# DIO-BNC.net
KiCad netlist of a schematic drawn in Altium Designer
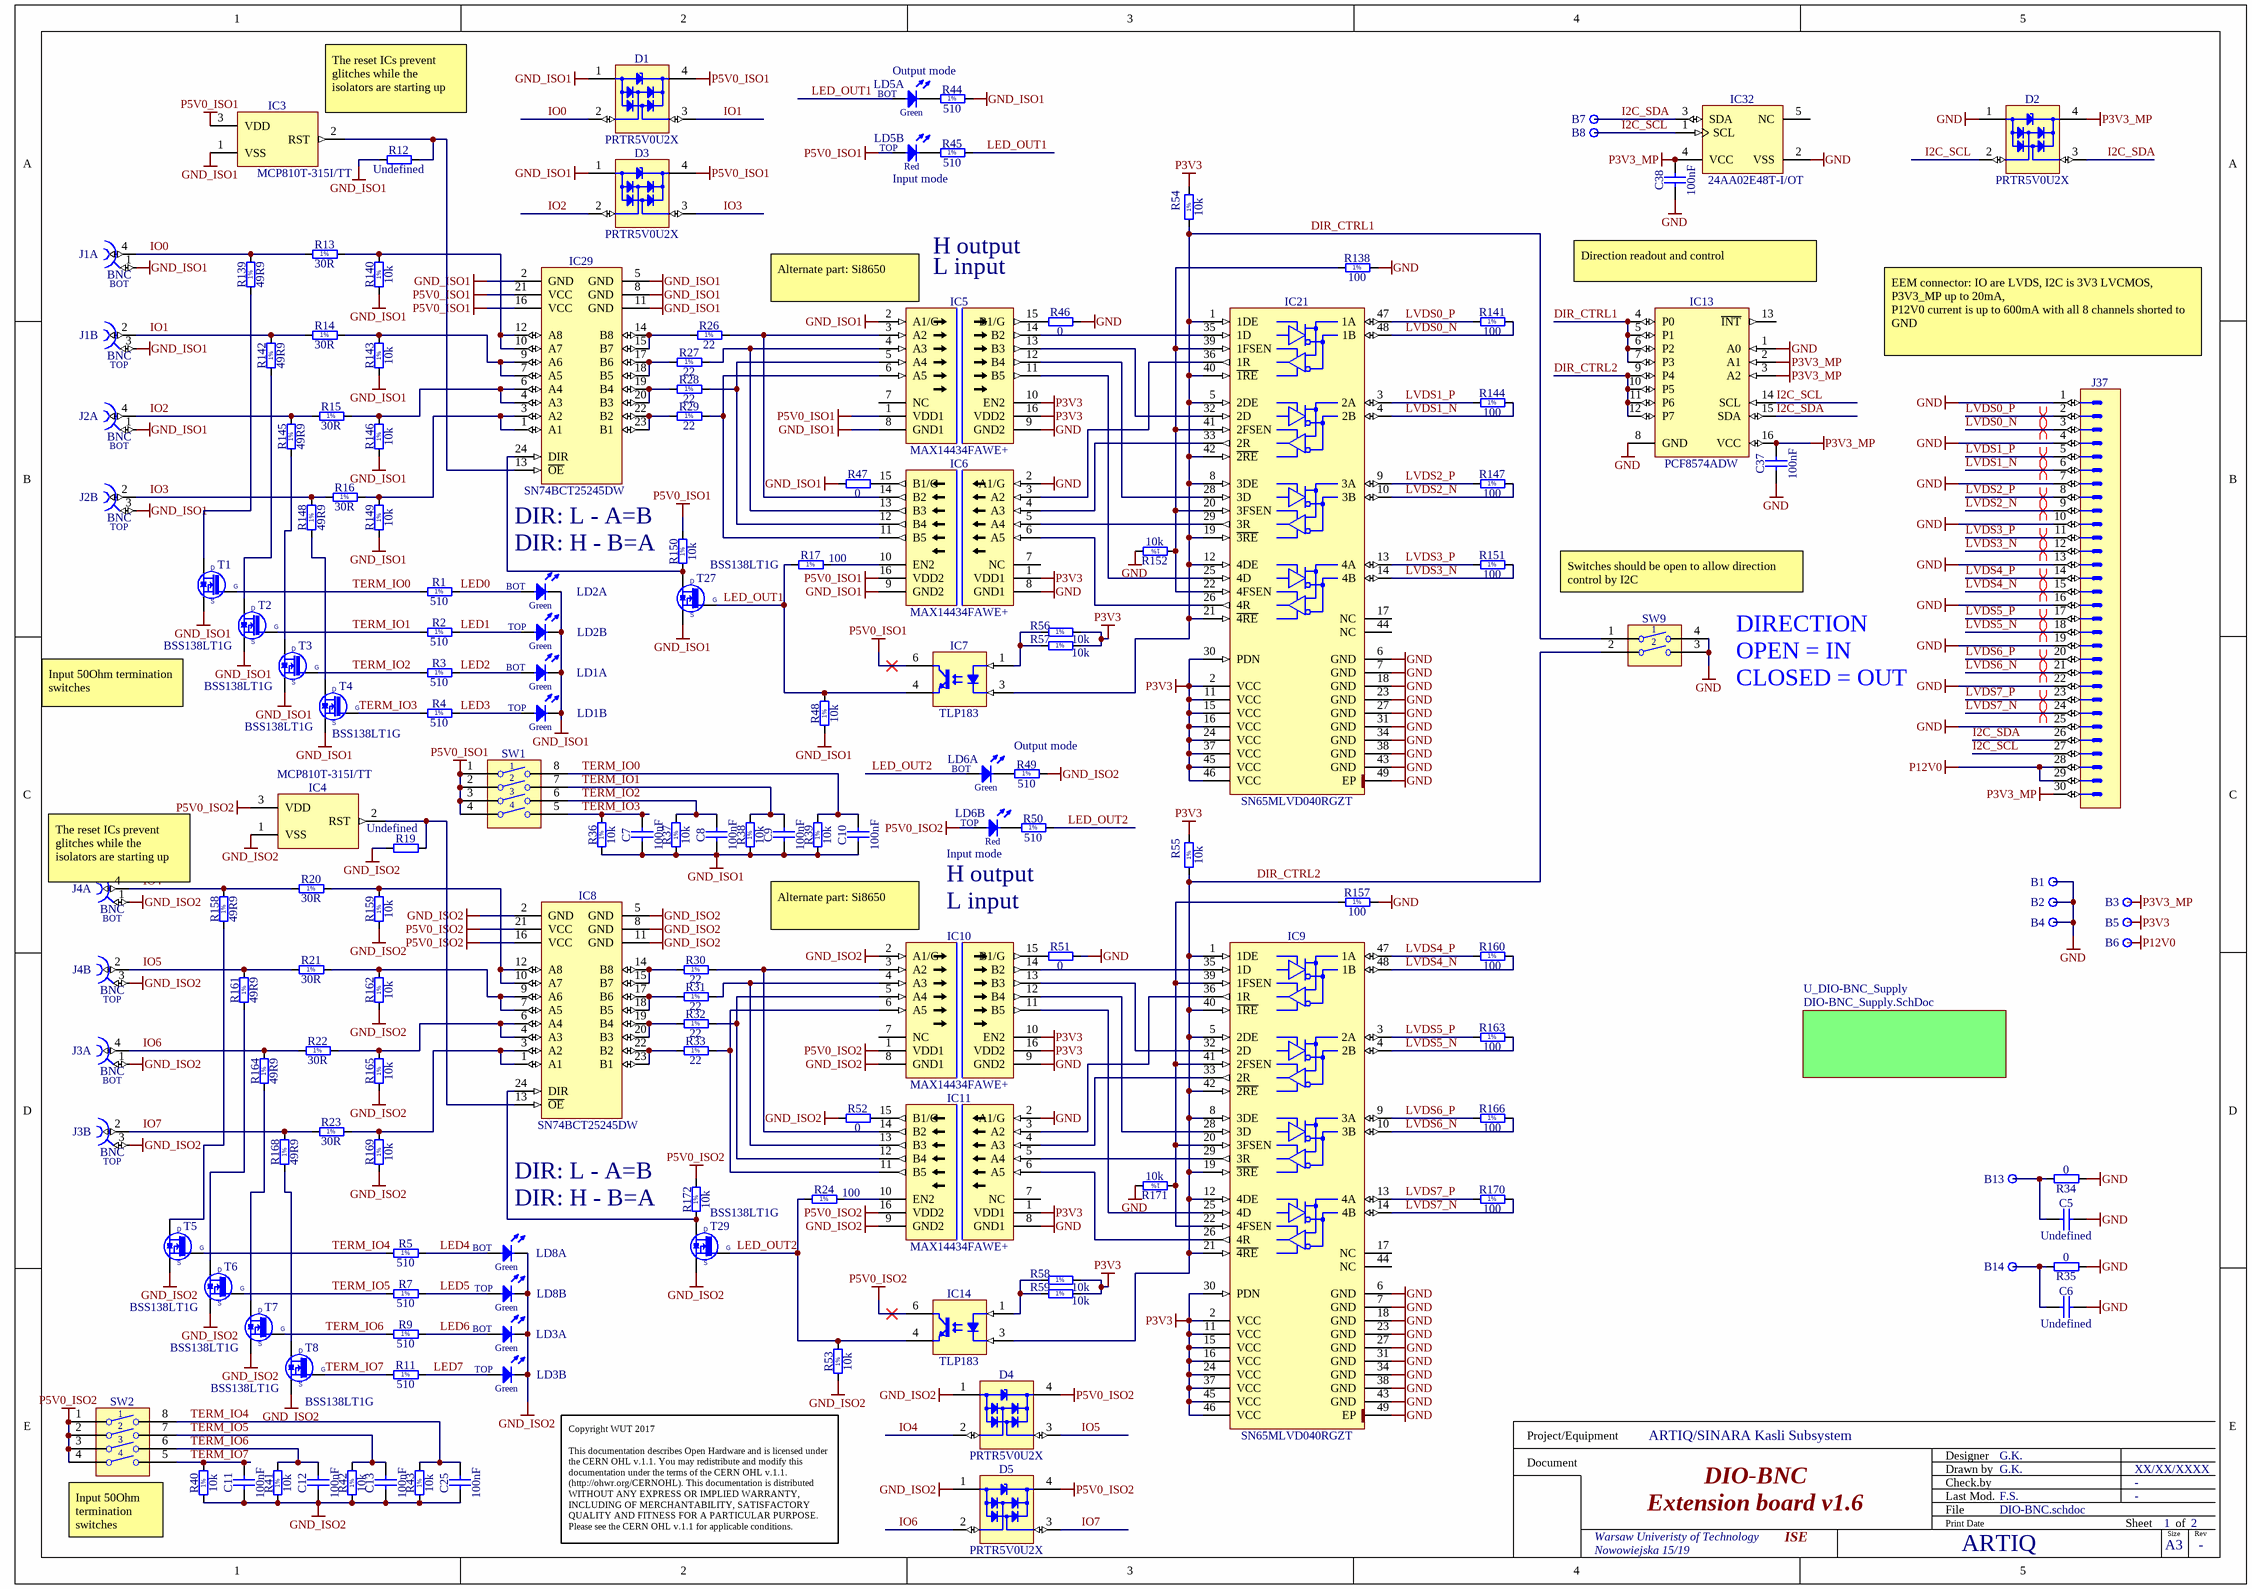
[diagram p0: DIO-BNC.schdoc]

(export (version "E")
  (design (tool "Eeschema 10.0.6"))
  (components
    (comp (ref "B1")
      (value "Plated Hole")
      (footprint "c130h60")
      (description "Single Terminal Socket")
      (fields (field (name "PART NUMBER") "PLATED_HOLE0.6_PAD1.3") (field (name "AUTHOR") "CERN DEM MR"))
      (libsource (lib "Eletro-mechanical") (part "Single Terminal Socket"))
    )
    (comp (ref "B2")
      (value "Plated Hole")
      (footprint "c130h60")
      (description "Single Terminal Socket")
      (fields (field (name "PART NUMBER") "PLATED_HOLE0.6_PAD1.3") (field (name "AUTHOR") "CERN DEM MR"))
      (libsource (lib "Eletro-mechanical") (part "Single Terminal Socket"))
    )
    (comp (ref "B3")
      (value "Plated Hole")
      (footprint "c130h60")
      (description "Single Terminal Socket")
      (fields (field (name "PART NUMBER") "PLATED_HOLE0.6_PAD1.3") (field (name "AUTHOR") "CERN DEM MR"))
      (libsource (lib "Eletro-mechanical") (part "Single Terminal Socket"))
    )
    (comp (ref "B4")
      (value "Plated Hole")
      (footprint "c130h60")
      (description "Single Terminal Socket")
      (fields (field (name "PART NUMBER") "PLATED_HOLE0.6_PAD1.3") (field (name "AUTHOR") "CERN DEM MR"))
      (libsource (lib "Eletro-mechanical") (part "Single Terminal Socket"))
    )
    (comp (ref "B5")
      (value "Plated Hole")
      (footprint "c130h60")
      (description "Single Terminal Socket")
      (fields (field (name "PART NUMBER") "PLATED_HOLE0.6_PAD1.3") (field (name "AUTHOR") "CERN DEM MR"))
      (libsource (lib "Eletro-mechanical") (part "Single Terminal Socket"))
    )
    (comp (ref "B6")
      (value "Plated Hole")
      (footprint "c130h60")
      (description "Single Terminal Socket")
      (fields (field (name "PART NUMBER") "PLATED_HOLE0.6_PAD1.3") (field (name "AUTHOR") "CERN DEM MR"))
      (libsource (lib "Eletro-mechanical") (part "Single Terminal Socket"))
    )
    (comp (ref "B7")
      (value "Plated Hole")
      (footprint "c130h60")
      (description "Single Terminal Socket")
      (fields (field (name "PART NUMBER") "PLATED_HOLE0.6_PAD1.3") (field (name "AUTHOR") "CERN DEM MR"))
      (libsource (lib "Eletro-mechanical") (part "Single Terminal Socket"))
    )
    (comp (ref "B8")
      (value "Plated Hole")
      (footprint "c130h60")
      (description "Single Terminal Socket")
      (fields (field (name "PART NUMBER") "PLATED_HOLE0.6_PAD1.3") (field (name "AUTHOR") "CERN DEM MR"))
      (libsource (lib "Eletro-mechanical") (part "Single Terminal Socket"))
    )
    (comp (ref "B13")
      (value "Plated Hole")
      (footprint "MTG270_500")
      (description "Single Terminal Socket")
      (fields (field (name "PART NUMBER") "PLATED_HOLE2.7_PAD5.0") (field (name "AUTHOR") "CERN DEM JMW"))
      (libsource (lib "Eletro-mechanical") (part "Single Terminal Socket"))
    )
    (comp (ref "B14")
      (value "Plated Hole")
      (footprint "MTG270_500")
      (description "Single Terminal Socket")
      (fields (field (name "PART NUMBER") "PLATED_HOLE2.7_PAD5.0") (field (name "AUTHOR") "CERN DEM JMW"))
      (libsource (lib "Eletro-mechanical") (part "Single Terminal Socket"))
    )
    (comp (ref "C5")
      (value "Undefined")
      (footprint "CAPC2012X135N")
      (description "Non-polarised capacitor")
      (fields (field (name "PART NUMBER") "CC0805_NO-VALUE") (field (name "AUTHOR") "CERN DEM JLC"))
      (libsource (lib "Capacitors") (part "Capacitor - non polarized"))
    )
    (comp (ref "C6")
      (value "Undefined")
      (footprint "CAPC2012X135N")
      (description "Non-polarised capacitor")
      (fields (field (name "PART NUMBER") "CC0805_NO-VALUE") (field (name "AUTHOR") "CERN DEM JLC"))
      (libsource (lib "Capacitors") (part "Capacitor - non polarized"))
    )
    (comp (ref "C7")
      (value "100nF")
      (footprint "CAPC1005X55N")
      (description "Non-polarised capacitor")
      (fields
        (field (name "PART NUMBER") "CC0402_100NF_16V_10%_X5R")
        (field (name "VOLTAGE") "16V")
        (field (name "AUTHOR") "CERN DEM JLC")
      )
      (libsource (lib "Capacitors") (part "Capacitor - non polarized"))
    )
    (comp (ref "C8")
      (value "100nF")
      (footprint "CAPC1005X55N")
      (description "Non-polarised capacitor")
      (fields
        (field (name "PART NUMBER") "CC0402_100NF_16V_10%_X5R")
        (field (name "VOLTAGE") "16V")
        (field (name "AUTHOR") "CERN DEM JLC")
      )
      (libsource (lib "Capacitors") (part "Capacitor - non polarized"))
    )
    (comp (ref "C9")
      (value "100nF")
      (footprint "CAPC1005X55N")
      (description "Non-polarised capacitor")
      (fields
        (field (name "PART NUMBER") "CC0402_100NF_16V_10%_X5R")
        (field (name "VOLTAGE") "16V")
        (field (name "AUTHOR") "CERN DEM JLC")
      )
      (libsource (lib "Capacitors") (part "Capacitor - non polarized"))
    )
    (comp (ref "C10")
      (value "100nF")
      (footprint "CAPC1005X55N")
      (description "Non-polarised capacitor")
      (fields
        (field (name "PART NUMBER") "CC0402_100NF_16V_10%_X5R")
        (field (name "VOLTAGE") "16V")
        (field (name "AUTHOR") "CERN DEM JLC")
      )
      (libsource (lib "Capacitors") (part "Capacitor - non polarized"))
    )
    (comp (ref "C11")
      (value "100nF")
      (footprint "CAPC1005X55N")
      (description "Non-polarised capacitor")
      (fields
        (field (name "PART NUMBER") "CC0402_100NF_16V_10%_X5R")
        (field (name "VOLTAGE") "16V")
        (field (name "AUTHOR") "CERN DEM JLC")
      )
      (libsource (lib "Capacitors") (part "Capacitor - non polarized"))
    )
    (comp (ref "C12")
      (value "100nF")
      (footprint "CAPC1005X55N")
      (description "Non-polarised capacitor")
      (fields
        (field (name "PART NUMBER") "CC0402_100NF_16V_10%_X5R")
        (field (name "VOLTAGE") "16V")
        (field (name "AUTHOR") "CERN DEM JLC")
      )
      (libsource (lib "Capacitors") (part "Capacitor - non polarized"))
    )
    (comp (ref "C13")
      (value "100nF")
      (footprint "CAPC1005X55N")
      (description "Non-polarised capacitor")
      (fields
        (field (name "PART NUMBER") "CC0402_100NF_16V_10%_X5R")
        (field (name "VOLTAGE") "16V")
        (field (name "AUTHOR") "CERN DEM JLC")
      )
      (libsource (lib "Capacitors") (part "Capacitor - non polarized"))
    )
    (comp (ref "C25")
      (value "100nF")
      (footprint "CAPC1005X55N")
      (description "Non-polarised capacitor")
      (fields
        (field (name "PART NUMBER") "CC0402_100NF_16V_10%_X5R")
        (field (name "VOLTAGE") "16V")
        (field (name "AUTHOR") "CERN DEM JLC")
      )
      (libsource (lib "Capacitors") (part "Capacitor - non polarized"))
    )
    (comp (ref "C37")
      (value "100nF")
      (footprint "CAPC1005X55N")
      (description "Non-polarised capacitor")
      (fields
        (field (name "PART NUMBER") "CC0402_100NF_16V_10%_X5R")
        (field (name "VOLTAGE") "16V")
        (field (name "AUTHOR") "CERN DEM JLC")
      )
      (libsource (lib "Capacitors") (part "Capacitor - non polarized"))
    )
    (comp (ref "C38")
      (value "100nF")
      (footprint "CAPC1005X55N")
      (description "Non-polarised capacitor")
      (fields
        (field (name "PART NUMBER") "CC0402_100NF_16V_10%_X5R")
        (field (name "VOLTAGE") "16V")
        (field (name "AUTHOR") "CERN DEM JLC")
      )
      (libsource (lib "Capacitors") (part "Capacitor - non polarized"))
    )
    (comp (ref "D1")
      (value "PRTR5V0U2X")
      (footprint "SOT190P230X110-4N")
      (description "Ultra Low Capacitance Double Rail-to-Rail ESD Protection Diode")
      (fields
        (field (name "VOLTAGE") "5.5V")
        (field (name "MANUFACTURER") "NXP SEMICONDUCTORS")
        (field (name "AUTHOR") "CERN DEM JLC")
      )
      (libsource (lib "ICs And Semiconductors") (part "PRTR5V0U2X"))
    )
    (comp (ref "D2")
      (value "PRTR5V0U2X")
      (footprint "SOT190P230X110-4N")
      (description "Ultra Low Capacitance Double Rail-to-Rail ESD Protection Diode")
      (fields
        (field (name "VOLTAGE") "5.5V")
        (field (name "MANUFACTURER") "NXP SEMICONDUCTORS")
        (field (name "AUTHOR") "CERN DEM JLC")
      )
      (libsource (lib "ICs And Semiconductors") (part "PRTR5V0U2X"))
    )
    (comp (ref "D3")
      (value "PRTR5V0U2X")
      (footprint "SOT190P230X110-4N")
      (description "Ultra Low Capacitance Double Rail-to-Rail ESD Protection Diode")
      (fields
        (field (name "VOLTAGE") "5.5V")
        (field (name "MANUFACTURER") "NXP SEMICONDUCTORS")
        (field (name "AUTHOR") "CERN DEM JLC")
      )
      (libsource (lib "ICs And Semiconductors") (part "PRTR5V0U2X"))
    )
    (comp (ref "D4")
      (value "PRTR5V0U2X")
      (footprint "SOT190P230X110-4N")
      (description "Ultra Low Capacitance Double Rail-to-Rail ESD Protection Diode")
      (fields
        (field (name "VOLTAGE") "5.5V")
        (field (name "MANUFACTURER") "NXP SEMICONDUCTORS")
        (field (name "AUTHOR") "CERN DEM JLC")
      )
      (libsource (lib "ICs And Semiconductors") (part "PRTR5V0U2X"))
    )
    (comp (ref "D5")
      (value "PRTR5V0U2X")
      (footprint "SOT190P230X110-4N")
      (description "Ultra Low Capacitance Double Rail-to-Rail ESD Protection Diode")
      (fields
        (field (name "VOLTAGE") "5.5V")
        (field (name "MANUFACTURER") "NXP SEMICONDUCTORS")
        (field (name "AUTHOR") "CERN DEM JLC")
      )
      (libsource (lib "ICs And Semiconductors") (part "PRTR5V0U2X"))
    )
    (comp (ref "IC3")
      (value "MCP810T-315I/TT")
      (footprint "SOT95P237X112-3N")
      (description "3.075V Microcontroller Supervisory Circuit With Push-Pull Output")
      (fields (field (name "MANUFACTURER") "MICROCHIP TECHNOLOGY") (field (name "AUTHOR") "GK"))
      (libsource (lib "LIBRARY_SCH") (part "VMON_MCP810"))
    )
    (comp (ref "IC4")
      (value "MCP810T-315I/TT")
      (footprint "SOT95P237X112-3N")
      (description "3.075V Microcontroller Supervisory Circuit With Push-Pull Output")
      (fields (field (name "MANUFACTURER") "MICROCHIP TECHNOLOGY") (field (name "AUTHOR") "GK"))
      (libsource (lib "LIBRARY_SCH") (part "VMON_MCP810"))
    )
    (comp (ref "IC5")
      (value "MAX14434FAWE+")
      (footprint "SOIC16 - SOIC16 wide")
      (description "Low Power Six-Channel Digital Isolator")
      (fields (field (name "MANUFACTURER") "MAX") (field (name "AUTHOR") "CERN DEM JLC"))
      (libsource (lib "") (part "Si8660_1"))
    )
    (comp (ref "IC6")
      (value "MAX14434FAWE+")
      (footprint "SOIC16 - SOIC16 wide")
      (description "Low Power Six-Channel Digital Isolator")
      (fields (field (name "MANUFACTURER") "MAX") (field (name "AUTHOR") "CERN DEM JLC"))
      (libsource (lib "ICs And Semiconductors") (part "Si8660"))
    )
    (comp (ref "IC7")
      (value "TLP183")
      (footprint "TOSHIBA_11-4M1S")
      (description "Single Optocoupler")
      (fields (field (name "MANUFACTURER") "TOSHIBA") (field (name "AUTHOR") "CERN DEM JMW"))
      (libsource (lib "ICs And Semiconductors") (part "Optocoupler Type1"))
    )
    (comp (ref "IC8")
      (value "SN74BCT25245DW")
      (footprint "SOIC127P1030X265-24N")
      (description "25 Ohms Octal Bus Transceiver With 3-State Outputs")
      (fields (field (name "MANUFACTURER") "TEXAS INSTRUMENTS") (field (name "AUTHOR") "CERN DEM JLC"))
      (libsource (lib "ICs And Semiconductors") (part "7425245"))
    )
    (comp (ref "IC9")
      (value "SN65MLVD040RGZT")
      (footprint "QFN50P700X700X100-49N-S420")
      (description "4-Channel Half-Duplex M-LVDS Line Transceiver")
      (fields (field (name "MANUFACTURER") "TEXAS INSTRUMENTS") (field (name "AUTHOR") "CERN DEM JLC"))
      (libsource (lib "ICs And Semiconductors") (part "SN65MLVD040"))
    )
    (comp (ref "IC10")
      (value "MAX14434FAWE+")
      (footprint "SOIC16 - SOIC16 wide")
      (description "Low Power Six-Channel Digital Isolator")
      (fields (field (name "MANUFACTURER") "MAX") (field (name "AUTHOR") "CERN DEM JLC"))
      (libsource (lib "") (part "Si8660_1"))
    )
    (comp (ref "IC11")
      (value "MAX14434FAWE+")
      (footprint "SOIC16 - SOIC16 wide")
      (description "Low Power Six-Channel Digital Isolator")
      (fields (field (name "MANUFACTURER") "MAX") (field (name "AUTHOR") "CERN DEM JLC"))
      (libsource (lib "ICs And Semiconductors") (part "Si8660"))
    )
    (comp (ref "IC13")
      (value "PCF8574ADW")
      (footprint "SOIC127P1030X265-16N")
      (description "Remote 8-bit I/O Expander For I2C Bus")
      (fields (field (name "MANUFACTURER") "TEXAS INSTRUMENTS") (field (name "AUTHOR") "CERN DEM JLC"))
      (libsource (lib "ICs And Semiconductors") (part "PCF8574ADW"))
    )
    (comp (ref "IC14")
      (value "TLP183")
      (footprint "TOSHIBA_11-4M1S")
      (description "Single Optocoupler")
      (fields (field (name "MANUFACTURER") "TOSHIBA") (field (name "AUTHOR") "CERN DEM JMW"))
      (libsource (lib "ICs And Semiconductors") (part "Optocoupler Type1"))
    )
    (comp (ref "IC21")
      (value "SN65MLVD040RGZT")
      (footprint "QFN50P700X700X100-49N-S420")
      (description "4-Channel Half-Duplex M-LVDS Line Transceiver")
      (fields (field (name "MANUFACTURER") "TEXAS INSTRUMENTS") (field (name "AUTHOR") "CERN DEM JLC"))
      (libsource (lib "ICs And Semiconductors") (part "SN65MLVD040"))
    )
    (comp (ref "IC29")
      (value "SN74BCT25245DW")
      (footprint "SOIC127P1030X265-24N")
      (description "25 Ohms Octal Bus Transceiver With 3-State Outputs")
      (fields (field (name "MANUFACTURER") "TEXAS INSTRUMENTS") (field (name "AUTHOR") "CERN DEM JLC"))
      (libsource (lib "ICs And Semiconductors") (part "7425245"))
    )
    (comp (ref "IC32")
      (value "24AA02E48T-I/OT")
      (footprint "SOT95P280X145-5N")
      (description "1.7V-5.5V, 2K I2C Serial EEPROM With EUI-48 Node Identity")
      (fields (field (name "MANUFACTURER") "MICROCHIP TECHNOLOGY") (field (name "AUTHOR") "CERN DEM MR"))
      (libsource (lib "ICs And Semiconductors") (part "24AA02E48T-I/OT"))
    )
    (comp (ref "J1")
      (value "BNC")
      (footprint "RENHOTEC_RHT-610-0049")
      (description "Dual Right Angle 50 Ohm BNC Jack, White Valox Case")
      (fields
        (field (name "PART NUMBER") "RENHOTEC_RHT-610-0049")
        (field (name "MANUFACTURER") "RENHOTEC")
        (field (name "AUTHOR") "GK")
      )
      (libsource (lib "LIBRARY_SCH") (part "CON_BNC_DUAL"))
    )
    (comp (ref "J2")
      (value "BNC")
      (footprint "RENHOTEC_RHT-610-0049")
      (description "Dual Right Angle 50 Ohm BNC Jack, White Valox Case")
      (fields
        (field (name "PART NUMBER") "RENHOTEC_RHT-610-0049")
        (field (name "MANUFACTURER") "RENHOTEC")
        (field (name "AUTHOR") "GK")
      )
      (libsource (lib "LIBRARY_SCH") (part "CON_BNC_DUAL"))
    )
    (comp (ref "J3")
      (value "BNC")
      (footprint "RENHOTEC_RHT-610-0049")
      (description "Dual Right Angle 50 Ohm BNC Jack, White Valox Case")
      (fields
        (field (name "PART NUMBER") "RENHOTEC_RHT-610-0049")
        (field (name "MANUFACTURER") "RENHOTEC")
        (field (name "AUTHOR") "GK")
      )
      (libsource (lib "LIBRARY_SCH") (part "CON_BNC_DUAL"))
    )
    (comp (ref "J4")
      (value "BNC")
      (footprint "RENHOTEC_RHT-610-0049")
      (description "Dual Right Angle 50 Ohm BNC Jack, White Valox Case")
      (fields
        (field (name "PART NUMBER") "RENHOTEC_RHT-610-0049")
        (field (name "MANUFACTURER") "RENHOTEC")
        (field (name "AUTHOR") "GK")
      )
      (libsource (lib "LIBRARY_SCH") (part "CON_BNC_DUAL"))
    )
    (comp (ref "J37")
      (value "~")
      (footprint "3M_N2530-6002RB")
      (description "Connector 30 Male")
      (fields
        (field (name "PART NUMBER") "3M_N2530-6002RB")
        (field (name "MANUFACTURER") "3M")
        (field (name "AUTHOR") "CERN DEM JLC")
      )
      (libsource (lib "Connectors") (part "Connector 30 Male"))
    )
    (comp (ref "LD1")
      (value "Green/Green")
      (footprint "LED_DIALIGHT_571-0122F")
      (description "LED x2 Green 1C2A-BOT_3C4A-TOP")
      (fields
        (field (name "PART NUMBER") "LED_DIALIGHT_571-0122F")
        (field (name "MANUFACTURER") "DIALIGHT")
        (field (name "AUTHOR") "CERN DEM JLC")
      )
      (libsource (lib "ICs And Semiconductors") (part "LED x2 Green 1C2A-BOT_3C4A-TOP"))
    )
    (comp (ref "LD2")
      (value "Green/Green")
      (footprint "LED_DIALIGHT_571-0122F")
      (description "LED x2 Green 1C2A-BOT_3C4A-TOP")
      (fields
        (field (name "PART NUMBER") "LED_DIALIGHT_571-0122F")
        (field (name "MANUFACTURER") "DIALIGHT")
        (field (name "AUTHOR") "CERN DEM JLC")
      )
      (libsource (lib "ICs And Semiconductors") (part "LED x2 Green 1C2A-BOT_3C4A-TOP"))
    )
    (comp (ref "LD3")
      (value "Green/Green")
      (footprint "LED_DIALIGHT_571-0122F")
      (description "LED x2 Green 1C2A-BOT_3C4A-TOP")
      (fields
        (field (name "PART NUMBER") "LED_DIALIGHT_571-0122F")
        (field (name "MANUFACTURER") "DIALIGHT")
        (field (name "AUTHOR") "CERN DEM JLC")
      )
      (libsource (lib "ICs And Semiconductors") (part "LED x2 Green 1C2A-BOT_3C4A-TOP"))
    )
    (comp (ref "LD5")
      (value "Red/Green")
      (footprint "LED_DIALIGHT_571-0112F")
      (description "2x LED  Botom Green, Top Red")
      (fields
        (field (name "PART NUMBER") "LED_DIALIGHT_571-0112F")
        (field (name "MANUFACTURER") "DIALIGHT")
        (field (name "AUTHOR") "CERN DEM JLC")
      )
      (libsource (lib "ICs And Semiconductors") (part "LED x2 G-1C2A-BOT_R-3C4A-TOP"))
    )
    (comp (ref "LD6")
      (value "Red/Green")
      (footprint "LED_DIALIGHT_571-0112F")
      (description "2x LED  Botom Green, Top Red")
      (fields
        (field (name "PART NUMBER") "LED_DIALIGHT_571-0112F")
        (field (name "MANUFACTURER") "DIALIGHT")
        (field (name "AUTHOR") "CERN DEM JLC")
      )
      (libsource (lib "ICs And Semiconductors") (part "LED x2 G-1C2A-BOT_R-3C4A-TOP"))
    )
    (comp (ref "LD8")
      (value "Green/Green")
      (footprint "LED_DIALIGHT_571-0122F")
      (description "LED x2 Green 1C2A-BOT_3C4A-TOP")
      (fields
        (field (name "PART NUMBER") "LED_DIALIGHT_571-0122F")
        (field (name "MANUFACTURER") "DIALIGHT")
        (field (name "AUTHOR") "CERN DEM JLC")
      )
      (libsource (lib "ICs And Semiconductors") (part "LED x2 Green 1C2A-BOT_3C4A-TOP"))
    )
    (comp (ref "R1")
      (value "510")
      (footprint "RESC1005X40N")
      (description "Resistor - 1%")
      (fields
        (field (name "PART NUMBER") "R0402_510R_1%_0.0625W_100PPM")
        (field (name "POWER") "0.0625W")
        (field (name "AUTHOR") "CERN DEM JLC")
      )
      (libsource (lib "Resistors") (part "Resistor - 1%"))
    )
    (comp (ref "R2")
      (value "510")
      (footprint "RESC1005X40N")
      (description "Resistor - 1%")
      (fields
        (field (name "PART NUMBER") "R0402_510R_1%_0.0625W_100PPM")
        (field (name "POWER") "0.0625W")
        (field (name "AUTHOR") "CERN DEM JLC")
      )
      (libsource (lib "Resistors") (part "Resistor - 1%"))
    )
    (comp (ref "R3")
      (value "510")
      (footprint "RESC1005X40N")
      (description "Resistor - 1%")
      (fields
        (field (name "PART NUMBER") "R0402_510R_1%_0.0625W_100PPM")
        (field (name "POWER") "0.0625W")
        (field (name "AUTHOR") "CERN DEM JLC")
      )
      (libsource (lib "Resistors") (part "Resistor - 1%"))
    )
    (comp (ref "R4")
      (value "510")
      (footprint "RESC1005X40N")
      (description "Resistor - 1%")
      (fields
        (field (name "PART NUMBER") "R0402_510R_1%_0.0625W_100PPM")
        (field (name "POWER") "0.0625W")
        (field (name "AUTHOR") "CERN DEM JLC")
      )
      (libsource (lib "Resistors") (part "Resistor - 1%"))
    )
    (comp (ref "R5")
      (value "510")
      (footprint "RESC1005X40N")
      (description "Resistor - 1%")
      (fields
        (field (name "PART NUMBER") "R0402_510R_1%_0.0625W_100PPM")
        (field (name "POWER") "0.0625W")
        (field (name "AUTHOR") "CERN DEM JLC")
      )
      (libsource (lib "Resistors") (part "Resistor - 1%"))
    )
    (comp (ref "R7")
      (value "510")
      (footprint "RESC1005X40N")
      (description "Resistor - 1%")
      (fields
        (field (name "PART NUMBER") "R0402_510R_1%_0.0625W_100PPM")
        (field (name "POWER") "0.0625W")
        (field (name "AUTHOR") "CERN DEM JLC")
      )
      (libsource (lib "Resistors") (part "Resistor - 1%"))
    )
    (comp (ref "R9")
      (value "510")
      (footprint "RESC1005X40N")
      (description "Resistor - 1%")
      (fields
        (field (name "PART NUMBER") "R0402_510R_1%_0.0625W_100PPM")
        (field (name "POWER") "0.0625W")
        (field (name "AUTHOR") "CERN DEM JLC")
      )
      (libsource (lib "Resistors") (part "Resistor - 1%"))
    )
    (comp (ref "R11")
      (value "510")
      (footprint "RESC1005X40N")
      (description "Resistor - 1%")
      (fields
        (field (name "PART NUMBER") "R0402_510R_1%_0.0625W_100PPM")
        (field (name "POWER") "0.0625W")
        (field (name "AUTHOR") "CERN DEM JLC")
      )
      (libsource (lib "Resistors") (part "Resistor - 1%"))
    )
    (comp (ref "R12")
      (value "Undefined")
      (footprint "RESC1005X40N")
      (description "Resistor")
      (fields (field (name "PART NUMBER") "R0402_NO-VALUE") (field (name "AUTHOR") "CERN DEM JLC"))
      (libsource (lib "Resistors") (part "Resistor"))
    )
    (comp (ref "R13")
      (value "30R")
      (footprint "RESC3225X70N")
      (description "Resistor - 5%")
      (fields
        (field (name "PART NUMBER") "R1210_30R_5%_0.5W_200ppm")
        (field (name "POWER") "0.5W")
        (field (name "AUTHOR") "CERN DEM JMW")
      )
      (libsource (lib "LIBRARY_SCH") (part "R1210_30R_5%_0.5W_200PPM"))
    )
    (comp (ref "R14")
      (value "30R")
      (footprint "RESC3225X70N")
      (description "Resistor - 5%")
      (fields
        (field (name "PART NUMBER") "R1210_30R_5%_0.5W_200ppm")
        (field (name "POWER") "0.5W")
        (field (name "AUTHOR") "CERN DEM JMW")
      )
      (libsource (lib "LIBRARY_SCH") (part "R1210_30R_5%_0.5W_200PPM"))
    )
    (comp (ref "R15")
      (value "30R")
      (footprint "RESC3225X70N")
      (description "Resistor - 5%")
      (fields
        (field (name "PART NUMBER") "R1210_30R_5%_0.5W_200ppm")
        (field (name "POWER") "0.5W")
        (field (name "AUTHOR") "CERN DEM JMW")
      )
      (libsource (lib "LIBRARY_SCH") (part "R1210_30R_5%_0.5W_200PPM"))
    )
    (comp (ref "R16")
      (value "30R")
      (footprint "RESC3225X70N")
      (description "Resistor - 5%")
      (fields
        (field (name "PART NUMBER") "R1210_30R_5%_0.5W_200ppm")
        (field (name "POWER") "0.5W")
        (field (name "AUTHOR") "CERN DEM JMW")
      )
      (libsource (lib "LIBRARY_SCH") (part "R1210_30R_5%_0.5W_200PPM"))
    )
    (comp (ref "R17")
      (value "100")
      (footprint "RESC1005X40N")
      (description "Resistor - 1%")
      (fields
        (field (name "PART NUMBER") "R0402_100R_1%_0.1W_100PPM")
        (field (name "POWER") "0.1W")
        (field (name "AUTHOR") "CERN DEM JLC")
      )
      (libsource (lib "Resistors") (part "Resistor - 1%"))
    )
    (comp (ref "R19")
      (value "Undefined")
      (footprint "RESC1005X40N")
      (description "Resistor")
      (fields (field (name "PART NUMBER") "R0402_NO-VALUE") (field (name "AUTHOR") "CERN DEM JLC"))
      (libsource (lib "Resistors") (part "Resistor"))
    )
    (comp (ref "R20")
      (value "30R")
      (footprint "RESC3225X70N")
      (description "Resistor - 5%")
      (fields
        (field (name "PART NUMBER") "R1210_30R_5%_0.5W_200ppm")
        (field (name "POWER") "0.5W")
        (field (name "AUTHOR") "CERN DEM JMW")
      )
      (libsource (lib "LIBRARY_SCH") (part "R1210_30R_5%_0.5W_200PPM"))
    )
    (comp (ref "R21")
      (value "30R")
      (footprint "RESC3225X70N")
      (description "Resistor - 5%")
      (fields
        (field (name "PART NUMBER") "R1210_30R_5%_0.5W_200ppm")
        (field (name "POWER") "0.5W")
        (field (name "AUTHOR") "CERN DEM JMW")
      )
      (libsource (lib "LIBRARY_SCH") (part "R1210_30R_5%_0.5W_200PPM"))
    )
    (comp (ref "R22")
      (value "30R")
      (footprint "RESC3225X70N")
      (description "Resistor - 5%")
      (fields
        (field (name "PART NUMBER") "R1210_30R_5%_0.5W_200ppm")
        (field (name "POWER") "0.5W")
        (field (name "AUTHOR") "CERN DEM JMW")
      )
      (libsource (lib "LIBRARY_SCH") (part "R1210_30R_5%_0.5W_200PPM"))
    )
    (comp (ref "R23")
      (value "30R")
      (footprint "RESC3225X70N")
      (description "Resistor - 5%")
      (fields
        (field (name "PART NUMBER") "R1210_30R_5%_0.5W_200ppm")
        (field (name "POWER") "0.5W")
        (field (name "AUTHOR") "CERN DEM JMW")
      )
      (libsource (lib "LIBRARY_SCH") (part "R1210_30R_5%_0.5W_200PPM"))
    )
    (comp (ref "R24")
      (value "100")
      (footprint "RESC1005X40N")
      (description "Resistor - 1%")
      (fields
        (field (name "PART NUMBER") "R0402_100R_1%_0.1W_100PPM")
        (field (name "POWER") "0.1W")
        (field (name "AUTHOR") "CERN DEM JLC")
      )
      (libsource (lib "Resistors") (part "Resistor - 1%"))
    )
    (comp (ref "R26")
      (value "22")
      (footprint "RESC1005X40N")
      (description "Resistor - 1%")
      (fields
        (field (name "PART NUMBER") "R0402_22R_1%_0.0625W_100PPM")
        (field (name "POWER") "0.0625W")
        (field (name "AUTHOR") "CERN DEM JLC")
      )
      (libsource (lib "Resistors") (part "Resistor - 1%"))
    )
    (comp (ref "R27")
      (value "22")
      (footprint "RESC1005X40N")
      (description "Resistor - 1%")
      (fields
        (field (name "PART NUMBER") "R0402_22R_1%_0.0625W_100PPM")
        (field (name "POWER") "0.0625W")
        (field (name "AUTHOR") "CERN DEM JLC")
      )
      (libsource (lib "Resistors") (part "Resistor - 1%"))
    )
    (comp (ref "R28")
      (value "22")
      (footprint "RESC1005X40N")
      (description "Resistor - 1%")
      (fields
        (field (name "PART NUMBER") "R0402_22R_1%_0.0625W_100PPM")
        (field (name "POWER") "0.0625W")
        (field (name "AUTHOR") "CERN DEM JLC")
      )
      (libsource (lib "Resistors") (part "Resistor - 1%"))
    )
    (comp (ref "R29")
      (value "22")
      (footprint "RESC1005X40N")
      (description "Resistor - 1%")
      (fields
        (field (name "PART NUMBER") "R0402_22R_1%_0.0625W_100PPM")
        (field (name "POWER") "0.0625W")
        (field (name "AUTHOR") "CERN DEM JLC")
      )
      (libsource (lib "Resistors") (part "Resistor - 1%"))
    )
    (comp (ref "R30")
      (value "22")
      (footprint "RESC1005X40N")
      (description "Resistor - 1%")
      (fields
        (field (name "PART NUMBER") "R0402_22R_1%_0.0625W_100PPM")
        (field (name "POWER") "0.0625W")
        (field (name "AUTHOR") "CERN DEM JLC")
      )
      (libsource (lib "Resistors") (part "Resistor - 1%"))
    )
    (comp (ref "R31")
      (value "22")
      (footprint "RESC1005X40N")
      (description "Resistor - 1%")
      (fields
        (field (name "PART NUMBER") "R0402_22R_1%_0.0625W_100PPM")
        (field (name "POWER") "0.0625W")
        (field (name "AUTHOR") "CERN DEM JLC")
      )
      (libsource (lib "Resistors") (part "Resistor - 1%"))
    )
    (comp (ref "R32")
      (value "22")
      (footprint "RESC1005X40N")
      (description "Resistor - 1%")
      (fields
        (field (name "PART NUMBER") "R0402_22R_1%_0.0625W_100PPM")
        (field (name "POWER") "0.0625W")
        (field (name "AUTHOR") "CERN DEM JLC")
      )
      (libsource (lib "Resistors") (part "Resistor - 1%"))
    )
    (comp (ref "R33")
      (value "22")
      (footprint "RESC1005X40N")
      (description "Resistor - 1%")
      (fields
        (field (name "PART NUMBER") "R0402_22R_1%_0.0625W_100PPM")
        (field (name "POWER") "0.0625W")
        (field (name "AUTHOR") "CERN DEM JLC")
      )
      (libsource (lib "Resistors") (part "Resistor - 1%"))
    )
    (comp (ref "R34")
      (value "0")
      (footprint "RESC1608X55N")
      (description "Resistor")
      (fields
        (field (name "PART NUMBER") "R0603_0R_JUMPER")
        (field (name "MANUFACTURER") "GENERIC")
        (field (name "AUTHOR") "CERN DEM JLC")
      )
      (libsource (lib "Resistors") (part "Resistor"))
    )
    (comp (ref "R35")
      (value "0")
      (footprint "RESC1608X55N")
      (description "Resistor")
      (fields
        (field (name "PART NUMBER") "R0603_0R_JUMPER")
        (field (name "MANUFACTURER") "GENERIC")
        (field (name "AUTHOR") "CERN DEM JLC")
      )
      (libsource (lib "Resistors") (part "Resistor"))
    )
    (comp (ref "R36")
      (value "10k")
      (footprint "RESC1005X40N")
      (description "Resistor - 1%")
      (fields
        (field (name "PART NUMBER") "R0402_10K_1%_0.0625W_100PPM")
        (field (name "POWER") "0.0625W")
        (field (name "AUTHOR") "CERN DEM JLC")
      )
      (libsource (lib "Resistors") (part "Resistor - 1%"))
    )
    (comp (ref "R37")
      (value "10k")
      (footprint "RESC1005X40N")
      (description "Resistor - 1%")
      (fields
        (field (name "PART NUMBER") "R0402_10K_1%_0.0625W_100PPM")
        (field (name "POWER") "0.0625W")
        (field (name "AUTHOR") "CERN DEM JLC")
      )
      (libsource (lib "Resistors") (part "Resistor - 1%"))
    )
    (comp (ref "R38")
      (value "10k")
      (footprint "RESC1005X40N")
      (description "Resistor - 1%")
      (fields
        (field (name "PART NUMBER") "R0402_10K_1%_0.0625W_100PPM")
        (field (name "POWER") "0.0625W")
        (field (name "AUTHOR") "CERN DEM JLC")
      )
      (libsource (lib "Resistors") (part "Resistor - 1%"))
    )
    (comp (ref "R39")
      (value "10k")
      (footprint "RESC1005X40N")
      (description "Resistor - 1%")
      (fields
        (field (name "PART NUMBER") "R0402_10K_1%_0.0625W_100PPM")
        (field (name "POWER") "0.0625W")
        (field (name "AUTHOR") "CERN DEM JLC")
      )
      (libsource (lib "Resistors") (part "Resistor - 1%"))
    )
    (comp (ref "R40")
      (value "10k")
      (footprint "RESC1005X40N")
      (description "Resistor - 1%")
      (fields
        (field (name "PART NUMBER") "R0402_10K_1%_0.0625W_100PPM")
        (field (name "POWER") "0.0625W")
        (field (name "AUTHOR") "CERN DEM JLC")
      )
      (libsource (lib "Resistors") (part "Resistor - 1%"))
    )
    (comp (ref "R41")
      (value "10k")
      (footprint "RESC1005X40N")
      (description "Resistor - 1%")
      (fields
        (field (name "PART NUMBER") "R0402_10K_1%_0.0625W_100PPM")
        (field (name "POWER") "0.0625W")
        (field (name "AUTHOR") "CERN DEM JLC")
      )
      (libsource (lib "Resistors") (part "Resistor - 1%"))
    )
    (comp (ref "R42")
      (value "10k")
      (footprint "RESC1005X40N")
      (description "Resistor - 1%")
      (fields
        (field (name "PART NUMBER") "R0402_10K_1%_0.0625W_100PPM")
        (field (name "POWER") "0.0625W")
        (field (name "AUTHOR") "CERN DEM JLC")
      )
      (libsource (lib "Resistors") (part "Resistor - 1%"))
    )
    (comp (ref "R43")
      (value "10k")
      (footprint "RESC1005X40N")
      (description "Resistor - 1%")
      (fields
        (field (name "PART NUMBER") "R0402_10K_1%_0.0625W_100PPM")
        (field (name "POWER") "0.0625W")
        (field (name "AUTHOR") "CERN DEM JLC")
      )
      (libsource (lib "Resistors") (part "Resistor - 1%"))
    )
    (comp (ref "R44")
      (value "510")
      (footprint "RESC1005X40N")
      (description "Resistor - 1%")
      (fields
        (field (name "PART NUMBER") "R0402_510R_1%_0.0625W_100PPM")
        (field (name "POWER") "0.0625W")
        (field (name "AUTHOR") "CERN DEM JLC")
      )
      (libsource (lib "Resistors") (part "Resistor - 1%"))
    )
    (comp (ref "R45")
      (value "510")
      (footprint "RESC1005X40N")
      (description "Resistor - 1%")
      (fields
        (field (name "PART NUMBER") "R0402_510R_1%_0.0625W_100PPM")
        (field (name "POWER") "0.0625W")
        (field (name "AUTHOR") "CERN DEM JLC")
      )
      (libsource (lib "Resistors") (part "Resistor - 1%"))
    )
    (comp (ref "R46")
      (value "0")
      (footprint "RESC1005X40N")
      (description "Resistor")
      (fields
        (field (name "PART NUMBER") "R0402_0R_JUMPER")
        (field (name "MANUFACTURER") "GENERIC")
        (field (name "AUTHOR") "CERN DEM JLC")
      )
      (libsource (lib "Resistors") (part "Resistor"))
    )
    (comp (ref "R47")
      (value "0")
      (footprint "RESC1005X40N")
      (description "Resistor")
      (fields
        (field (name "PART NUMBER") "R0402_0R_JUMPER")
        (field (name "MANUFACTURER") "GENERIC")
        (field (name "AUTHOR") "CERN DEM JLC")
      )
      (libsource (lib "Resistors") (part "Resistor"))
    )
    (comp (ref "R48")
      (value "10k")
      (footprint "RESC1005X40N")
      (description "Resistor - 1%")
      (fields
        (field (name "PART NUMBER") "R0402_10K_1%_0.0625W_100PPM")
        (field (name "POWER") "0.0625W")
        (field (name "AUTHOR") "CERN DEM JLC")
      )
      (libsource (lib "Resistors") (part "Resistor - 1%"))
    )
    (comp (ref "R49")
      (value "510")
      (footprint "RESC1005X40N")
      (description "Resistor - 1%")
      (fields
        (field (name "PART NUMBER") "R0402_510R_1%_0.0625W_100PPM")
        (field (name "POWER") "0.0625W")
        (field (name "AUTHOR") "CERN DEM JLC")
      )
      (libsource (lib "Resistors") (part "Resistor - 1%"))
    )
    (comp (ref "R50")
      (value "510")
      (footprint "RESC1005X40N")
      (description "Resistor - 1%")
      (fields
        (field (name "PART NUMBER") "R0402_510R_1%_0.0625W_100PPM")
        (field (name "POWER") "0.0625W")
        (field (name "AUTHOR") "CERN DEM JLC")
      )
      (libsource (lib "Resistors") (part "Resistor - 1%"))
    )
    (comp (ref "R51")
      (value "0")
      (footprint "RESC1005X40N")
      (description "Resistor")
      (fields
        (field (name "PART NUMBER") "R0402_0R_JUMPER")
        (field (name "MANUFACTURER") "GENERIC")
        (field (name "AUTHOR") "CERN DEM JLC")
      )
      (libsource (lib "Resistors") (part "Resistor"))
    )
    (comp (ref "R52")
      (value "0")
      (footprint "RESC1005X40N")
      (description "Resistor")
      (fields
        (field (name "PART NUMBER") "R0402_0R_JUMPER")
        (field (name "MANUFACTURER") "GENERIC")
        (field (name "AUTHOR") "CERN DEM JLC")
      )
      (libsource (lib "Resistors") (part "Resistor"))
    )
    (comp (ref "R53")
      (value "10k")
      (footprint "RESC1005X40N")
      (description "Resistor - 1%")
      (fields
        (field (name "PART NUMBER") "R0402_10K_1%_0.0625W_100PPM")
        (field (name "POWER") "0.0625W")
        (field (name "AUTHOR") "CERN DEM JLC")
      )
      (libsource (lib "Resistors") (part "Resistor - 1%"))
    )
    (comp (ref "R54")
      (value "10k")
      (footprint "RESC1005X40N")
      (description "Resistor - 1%")
      (fields
        (field (name "PART NUMBER") "R0402_10K_1%_0.0625W_100PPM")
        (field (name "POWER") "0.0625W")
        (field (name "AUTHOR") "CERN DEM JLC")
      )
      (libsource (lib "Resistors") (part "Resistor - 1%"))
    )
    (comp (ref "R55")
      (value "10k")
      (footprint "RESC1005X40N")
      (description "Resistor - 1%")
      (fields
        (field (name "PART NUMBER") "R0402_10K_1%_0.0625W_100PPM")
        (field (name "POWER") "0.0625W")
        (field (name "AUTHOR") "CERN DEM JLC")
      )
      (libsource (lib "Resistors") (part "Resistor - 1%"))
    )
    (comp (ref "R56")
      (value "10k")
      (footprint "RESC1005X40N")
      (description "Resistor - 1%")
      (fields
        (field (name "PART NUMBER") "R0402_10K_1%_0.0625W_100PPM")
        (field (name "POWER") "0.0625W")
        (field (name "AUTHOR") "CERN DEM JLC")
      )
      (libsource (lib "Resistors") (part "Resistor - 1%"))
    )
    (comp (ref "R57")
      (value "10k")
      (footprint "RESC1005X40N")
      (description "Resistor - 1%")
      (fields
        (field (name "PART NUMBER") "R0402_10K_1%_0.0625W_100PPM")
        (field (name "POWER") "0.0625W")
        (field (name "AUTHOR") "CERN DEM JLC")
      )
      (libsource (lib "Resistors") (part "Resistor - 1%"))
    )
    (comp (ref "R58")
      (value "10k")
      (footprint "RESC1005X40N")
      (description "Resistor - 1%")
      (fields
        (field (name "PART NUMBER") "R0402_10K_1%_0.0625W_100PPM")
        (field (name "POWER") "0.0625W")
        (field (name "AUTHOR") "CERN DEM JLC")
      )
      (libsource (lib "Resistors") (part "Resistor - 1%"))
    )
    (comp (ref "R59")
      (value "10k")
      (footprint "RESC1005X40N")
      (description "Resistor - 1%")
      (fields
        (field (name "PART NUMBER") "R0402_10K_1%_0.0625W_100PPM")
        (field (name "POWER") "0.0625W")
        (field (name "AUTHOR") "CERN DEM JLC")
      )
      (libsource (lib "Resistors") (part "Resistor - 1%"))
    )
    (comp (ref "R138")
      (value "100")
      (footprint "RESC1005X40N")
      (description "Resistor - 1%")
      (fields
        (field (name "PART NUMBER") "R0402_100R_1%_0.1W_100PPM")
        (field (name "POWER") "0.1W")
        (field (name "AUTHOR") "CERN DEM JLC")
      )
      (libsource (lib "Resistors") (part "Resistor - 1%"))
    )
    (comp (ref "R139")
      (value "49R9")
      (footprint "RESC3225X70N")
      (description "Resistor - 1%")
      (fields
        (field (name "PART NUMBER") "R1210_49R9_1%_0.5W_100PPM_VISHAY_CRCW")
        (field (name "POWER") "0.5W")
        (field (name "AUTHOR") "CERN DEM JMW")
      )
      (libsource (lib "Resistors") (part "Resistor - 1%"))
    )
    (comp (ref "R140")
      (value "10k")
      (footprint "RESC1005X40N")
      (description "Resistor - 1%")
      (fields
        (field (name "PART NUMBER") "R0402_10K_1%_0.0625W_100PPM")
        (field (name "POWER") "0.0625W")
        (field (name "AUTHOR") "CERN DEM JLC")
      )
      (libsource (lib "Resistors") (part "Resistor - 1%"))
    )
    (comp (ref "R141")
      (value "100")
      (footprint "RESC1005X40N")
      (description "Resistor - 1%")
      (fields
        (field (name "PART NUMBER") "R0402_100R_1%_0.1W_100PPM")
        (field (name "POWER") "0.1W")
        (field (name "AUTHOR") "CERN DEM JLC")
      )
      (libsource (lib "Resistors") (part "Resistor - 1%"))
    )
    (comp (ref "R142")
      (value "49R9")
      (footprint "RESC3225X70N")
      (description "Resistor - 1%")
      (fields
        (field (name "PART NUMBER") "R1210_49R9_1%_0.5W_100PPM_VISHAY_CRCW")
        (field (name "POWER") "0.5W")
        (field (name "AUTHOR") "CERN DEM JMW")
      )
      (libsource (lib "Resistors") (part "Resistor - 1%"))
    )
    (comp (ref "R143")
      (value "10k")
      (footprint "RESC1005X40N")
      (description "Resistor - 1%")
      (fields
        (field (name "PART NUMBER") "R0402_10K_1%_0.0625W_100PPM")
        (field (name "POWER") "0.0625W")
        (field (name "AUTHOR") "CERN DEM JLC")
      )
      (libsource (lib "Resistors") (part "Resistor - 1%"))
    )
    (comp (ref "R144")
      (value "100")
      (footprint "RESC1005X40N")
      (description "Resistor - 1%")
      (fields
        (field (name "PART NUMBER") "R0402_100R_1%_0.1W_100PPM")
        (field (name "POWER") "0.1W")
        (field (name "AUTHOR") "CERN DEM JLC")
      )
      (libsource (lib "Resistors") (part "Resistor - 1%"))
    )
    (comp (ref "R145")
      (value "49R9")
      (footprint "RESC3225X70N")
      (description "Resistor - 1%")
      (fields
        (field (name "PART NUMBER") "R1210_49R9_1%_0.5W_100PPM_VISHAY_CRCW")
        (field (name "POWER") "0.5W")
        (field (name "AUTHOR") "CERN DEM JMW")
      )
      (libsource (lib "Resistors") (part "Resistor - 1%"))
    )
    (comp (ref "R146")
      (value "10k")
      (footprint "RESC1005X40N")
      (description "Resistor - 1%")
      (fields
        (field (name "PART NUMBER") "R0402_10K_1%_0.0625W_100PPM")
        (field (name "POWER") "0.0625W")
        (field (name "AUTHOR") "CERN DEM JLC")
      )
      (libsource (lib "Resistors") (part "Resistor - 1%"))
    )
    (comp (ref "R147")
      (value "100")
      (footprint "RESC1005X40N")
      (description "Resistor - 1%")
      (fields
        (field (name "PART NUMBER") "R0402_100R_1%_0.1W_100PPM")
        (field (name "POWER") "0.1W")
        (field (name "AUTHOR") "CERN DEM JLC")
      )
      (libsource (lib "Resistors") (part "Resistor - 1%"))
    )
    (comp (ref "R148")
      (value "49R9")
      (footprint "RESC3225X70N")
      (description "Resistor - 1%")
      (fields
        (field (name "PART NUMBER") "R1210_49R9_1%_0.5W_100PPM_VISHAY_CRCW")
        (field (name "POWER") "0.5W")
        (field (name "AUTHOR") "CERN DEM JMW")
      )
      (libsource (lib "Resistors") (part "Resistor - 1%"))
    )
    (comp (ref "R149")
      (value "10k")
      (footprint "RESC1005X40N")
      (description "Resistor - 1%")
      (fields
        (field (name "PART NUMBER") "R0402_10K_1%_0.0625W_100PPM")
        (field (name "POWER") "0.0625W")
        (field (name "AUTHOR") "CERN DEM JLC")
      )
      (libsource (lib "Resistors") (part "Resistor - 1%"))
    )
    (comp (ref "R150")
      (value "10k")
      (footprint "RESC1005X40N")
      (description "Resistor - 1%")
      (fields
        (field (name "PART NUMBER") "R0402_10K_1%_0.0625W_100PPM")
        (field (name "POWER") "0.0625W")
        (field (name "AUTHOR") "CERN DEM JLC")
      )
      (libsource (lib "Resistors") (part "Resistor - 1%"))
    )
    (comp (ref "R151")
      (value "100")
      (footprint "RESC1005X40N")
      (description "Resistor - 1%")
      (fields
        (field (name "PART NUMBER") "R0402_100R_1%_0.1W_100PPM")
        (field (name "POWER") "0.1W")
        (field (name "AUTHOR") "CERN DEM JLC")
      )
      (libsource (lib "Resistors") (part "Resistor - 1%"))
    )
    (comp (ref "R152")
      (value "10k")
      (footprint "RESC1005X40N")
      (description "Resistor - 1%")
      (fields
        (field (name "PART NUMBER") "R0402_10K_1%_0.0625W_100PPM")
        (field (name "POWER") "0.0625W")
        (field (name "AUTHOR") "CERN DEM JLC")
      )
      (libsource (lib "Resistors") (part "Resistor - 1%"))
    )
    (comp (ref "R157")
      (value "100")
      (footprint "RESC1005X40N")
      (description "Resistor - 1%")
      (fields
        (field (name "PART NUMBER") "R0402_100R_1%_0.1W_100PPM")
        (field (name "POWER") "0.1W")
        (field (name "AUTHOR") "CERN DEM JLC")
      )
      (libsource (lib "Resistors") (part "Resistor - 1%"))
    )
    (comp (ref "R158")
      (value "49R9")
      (footprint "RESC3225X70N")
      (description "Resistor - 1%")
      (fields
        (field (name "PART NUMBER") "R1210_49R9_1%_0.5W_100PPM_VISHAY_CRCW")
        (field (name "POWER") "0.5W")
        (field (name "AUTHOR") "CERN DEM JMW")
      )
      (libsource (lib "Resistors") (part "Resistor - 1%"))
    )
    (comp (ref "R159")
      (value "10k")
      (footprint "RESC1005X40N")
      (description "Resistor - 1%")
      (fields
        (field (name "PART NUMBER") "R0402_10K_1%_0.0625W_100PPM")
        (field (name "POWER") "0.0625W")
        (field (name "AUTHOR") "CERN DEM JLC")
      )
      (libsource (lib "Resistors") (part "Resistor - 1%"))
    )
    (comp (ref "R160")
      (value "100")
      (footprint "RESC1005X40N")
      (description "Resistor - 1%")
      (fields
        (field (name "PART NUMBER") "R0402_100R_1%_0.1W_100PPM")
        (field (name "POWER") "0.1W")
        (field (name "AUTHOR") "CERN DEM JLC")
      )
      (libsource (lib "Resistors") (part "Resistor - 1%"))
    )
    (comp (ref "R161")
      (value "49R9")
      (footprint "RESC3225X70N")
      (description "Resistor - 1%")
      (fields
        (field (name "PART NUMBER") "R1210_49R9_1%_0.5W_100PPM_VISHAY_CRCW")
        (field (name "POWER") "0.5W")
        (field (name "AUTHOR") "CERN DEM JMW")
      )
      (libsource (lib "Resistors") (part "Resistor - 1%"))
    )
    (comp (ref "R162")
      (value "10k")
      (footprint "RESC1005X40N")
      (description "Resistor - 1%")
      (fields
        (field (name "PART NUMBER") "R0402_10K_1%_0.0625W_100PPM")
        (field (name "POWER") "0.0625W")
        (field (name "AUTHOR") "CERN DEM JLC")
      )
      (libsource (lib "Resistors") (part "Resistor - 1%"))
    )
    (comp (ref "R163")
      (value "100")
      (footprint "RESC1005X40N")
      (description "Resistor - 1%")
      (fields
        (field (name "PART NUMBER") "R0402_100R_1%_0.1W_100PPM")
        (field (name "POWER") "0.1W")
        (field (name "AUTHOR") "CERN DEM JLC")
      )
      (libsource (lib "Resistors") (part "Resistor - 1%"))
    )
    (comp (ref "R164")
      (value "49R9")
      (footprint "RESC3225X70N")
      (description "Resistor - 1%")
      (fields
        (field (name "PART NUMBER") "R1210_49R9_1%_0.5W_100PPM_VISHAY_CRCW")
        (field (name "POWER") "0.5W")
        (field (name "AUTHOR") "CERN DEM JMW")
      )
      (libsource (lib "Resistors") (part "Resistor - 1%"))
    )
    (comp (ref "R165")
      (value "10k")
      (footprint "RESC1005X40N")
      (description "Resistor - 1%")
      (fields
        (field (name "PART NUMBER") "R0402_10K_1%_0.0625W_100PPM")
        (field (name "POWER") "0.0625W")
        (field (name "AUTHOR") "CERN DEM JLC")
      )
      (libsource (lib "Resistors") (part "Resistor - 1%"))
    )
    (comp (ref "R166")
      (value "100")
      (footprint "RESC1005X40N")
      (description "Resistor - 1%")
      (fields
        (field (name "PART NUMBER") "R0402_100R_1%_0.1W_100PPM")
        (field (name "POWER") "0.1W")
        (field (name "AUTHOR") "CERN DEM JLC")
      )
      (libsource (lib "Resistors") (part "Resistor - 1%"))
    )
    (comp (ref "R168")
      (value "49R9")
      (footprint "RESC3225X70N")
      (description "Resistor - 1%")
      (fields
        (field (name "PART NUMBER") "R1210_49R9_1%_0.5W_100PPM_VISHAY_CRCW")
        (field (name "POWER") "0.5W")
        (field (name "AUTHOR") "CERN DEM JMW")
      )
      (libsource (lib "Resistors") (part "Resistor - 1%"))
    )
    (comp (ref "R169")
      (value "10k")
      (footprint "RESC1005X40N")
      (description "Resistor - 1%")
      (fields
        (field (name "PART NUMBER") "R0402_10K_1%_0.0625W_100PPM")
        (field (name "POWER") "0.0625W")
        (field (name "AUTHOR") "CERN DEM JLC")
      )
      (libsource (lib "Resistors") (part "Resistor - 1%"))
    )
    (comp (ref "R170")
      (value "100")
      (footprint "RESC1005X40N")
      (description "Resistor - 1%")
      (fields
        (field (name "PART NUMBER") "R0402_100R_1%_0.1W_100PPM")
        (field (name "POWER") "0.1W")
        (field (name "AUTHOR") "CERN DEM JLC")
      )
      (libsource (lib "Resistors") (part "Resistor - 1%"))
    )
    (comp (ref "R171")
      (value "10k")
      (footprint "RESC1005X40N")
      (description "Resistor - 1%")
      (fields
        (field (name "PART NUMBER") "R0402_10K_1%_0.0625W_100PPM")
        (field (name "POWER") "0.0625W")
        (field (name "AUTHOR") "CERN DEM JLC")
      )
      (libsource (lib "Resistors") (part "Resistor - 1%"))
    )
    (comp (ref "R172")
      (value "10k")
      (footprint "RESC1005X40N")
      (description "Resistor - 1%")
      (fields
        (field (name "PART NUMBER") "R0402_10K_1%_0.0625W_100PPM")
        (field (name "POWER") "0.0625W")
        (field (name "AUTHOR") "CERN DEM JLC")
      )
      (libsource (lib "Resistors") (part "Resistor - 1%"))
    )
    (comp (ref "SW1")
      (value "Switch")
      (footprint "SW_OMRON_A6S-4102-H")
      (description "4 Ways SPST DIP Switch")
      (fields
        (field (name "PART NUMBER") "SW_OMRON_A6S-4102-H")
        (field (name "MANUFACTURER") "OMRON")
        (field (name "AUTHOR") "CERN DEM JMW")
      )
      (libsource (lib "Eletro-mechanical") (part "SW 4x SPST DIP Switch"))
    )
    (comp (ref "SW2")
      (value "Switch")
      (footprint "SW_OMRON_A6S-4102-H")
      (description "4 Ways SPST DIP Switch")
      (fields
        (field (name "PART NUMBER") "SW_OMRON_A6S-4102-H")
        (field (name "MANUFACTURER") "OMRON")
        (field (name "AUTHOR") "CERN DEM JMW")
      )
      (libsource (lib "Eletro-mechanical") (part "SW 4x SPST DIP Switch"))
    )
    (comp (ref "SW9")
      (value "Switch")
      (footprint "SW_OMRON_A6S-2102-H")
      (description "2 Ways SPST DIP Switch")
      (fields
        (field (name "PART NUMBER") "SW_OMRON_A6S-2102-H")
        (field (name "MANUFACTURER") "OMRON")
        (field (name "AUTHOR") "CERN DEM JMW")
      )
      (libsource (lib "Eletro-mechanical") (part "SW 2x SPST DIP Switch"))
    )
    (comp (ref "T1")
      (value "BSS138LT1G")
      (footprint "SOT95P240X110-3N")
      (description "N-CHANNEL MOSFET WITH DIODE")
      (fields (field (name "MANUFACTURER") "ON SEMICONDUCTOR") (field (name "AUTHOR") "CERN DEM JLC"))
      (libsource (lib "ICs And Semiconductors") (part "N-MOSFET-D 1G 2S 3D"))
    )
    (comp (ref "T2")
      (value "BSS138LT1G")
      (footprint "SOT95P240X110-3N")
      (description "N-CHANNEL MOSFET WITH DIODE")
      (fields (field (name "MANUFACTURER") "ON SEMICONDUCTOR") (field (name "AUTHOR") "CERN DEM JLC"))
      (libsource (lib "ICs And Semiconductors") (part "N-MOSFET-D 1G 2S 3D"))
    )
    (comp (ref "T3")
      (value "BSS138LT1G")
      (footprint "SOT95P240X110-3N")
      (description "N-CHANNEL MOSFET WITH DIODE")
      (fields (field (name "MANUFACTURER") "ON SEMICONDUCTOR") (field (name "AUTHOR") "CERN DEM JLC"))
      (libsource (lib "ICs And Semiconductors") (part "N-MOSFET-D 1G 2S 3D"))
    )
    (comp (ref "T4")
      (value "BSS138LT1G")
      (footprint "SOT95P240X110-3N")
      (description "N-CHANNEL MOSFET WITH DIODE")
      (fields (field (name "MANUFACTURER") "ON SEMICONDUCTOR") (field (name "AUTHOR") "CERN DEM JLC"))
      (libsource (lib "ICs And Semiconductors") (part "N-MOSFET-D 1G 2S 3D"))
    )
    (comp (ref "T5")
      (value "BSS138LT1G")
      (footprint "SOT95P240X110-3N")
      (description "N-CHANNEL MOSFET WITH DIODE")
      (fields (field (name "MANUFACTURER") "ON SEMICONDUCTOR") (field (name "AUTHOR") "CERN DEM JLC"))
      (libsource (lib "ICs And Semiconductors") (part "N-MOSFET-D 1G 2S 3D"))
    )
    (comp (ref "T6")
      (value "BSS138LT1G")
      (footprint "SOT95P240X110-3N")
      (description "N-CHANNEL MOSFET WITH DIODE")
      (fields (field (name "MANUFACTURER") "ON SEMICONDUCTOR") (field (name "AUTHOR") "CERN DEM JLC"))
      (libsource (lib "ICs And Semiconductors") (part "N-MOSFET-D 1G 2S 3D"))
    )
    (comp (ref "T7")
      (value "BSS138LT1G")
      (footprint "SOT95P240X110-3N")
      (description "N-CHANNEL MOSFET WITH DIODE")
      (fields (field (name "MANUFACTURER") "ON SEMICONDUCTOR") (field (name "AUTHOR") "CERN DEM JLC"))
      (libsource (lib "ICs And Semiconductors") (part "N-MOSFET-D 1G 2S 3D"))
    )
    (comp (ref "T8")
      (value "BSS138LT1G")
      (footprint "SOT95P240X110-3N")
      (description "N-CHANNEL MOSFET WITH DIODE")
      (fields (field (name "MANUFACTURER") "ON SEMICONDUCTOR") (field (name "AUTHOR") "CERN DEM JLC"))
      (libsource (lib "ICs And Semiconductors") (part "N-MOSFET-D 1G 2S 3D"))
    )
    (comp (ref "T27")
      (value "BSS138LT1G")
      (footprint "SOT95P240X110-3N")
      (description "N-CHANNEL MOSFET WITH DIODE")
      (fields (field (name "MANUFACTURER") "ON SEMICONDUCTOR") (field (name "AUTHOR") "CERN DEM JLC"))
      (libsource (lib "ICs And Semiconductors") (part "N-MOSFET-D 1G 2S 3D"))
    )
    (comp (ref "T29")
      (value "BSS138LT1G")
      (footprint "SOT95P240X110-3N")
      (description "N-CHANNEL MOSFET WITH DIODE")
      (fields (field (name "MANUFACTURER") "ON SEMICONDUCTOR") (field (name "AUTHOR") "CERN DEM JLC"))
      (libsource (lib "ICs And Semiconductors") (part "N-MOSFET-D 1G 2S 3D"))
    )
  )
  (nets
    (net (code "1") (name "/DIR_CTRL1") (class "Default")
      (node (ref "IC13") (pin "4") (pinfunction "P0_4") (pintype "bidirectional"))
      (node (ref "IC13") (pin "5") (pinfunction "P1_5") (pintype "bidirectional"))
      (node (ref "IC13") (pin "6") (pinfunction "P2_6") (pintype "bidirectional"))
      (node (ref "IC13") (pin "7") (pinfunction "P3_7") (pintype "bidirectional"))
      (node (ref "IC21") (pin "1") (pinfunction "1DE_1") (pintype "input"))
      (node (ref "IC21") (pin "12") (pinfunction "4DE_12") (pintype "input"))
      (node (ref "IC21") (pin "19") (pinfunction "~{3RE}_19") (pintype "input"))
      (node (ref "IC21") (pin "21") (pinfunction "~{4RE}_21") (pintype "input"))
      (node (ref "IC21") (pin "40") (pinfunction "~{1RE}_40") (pintype "input"))
      (node (ref "IC21") (pin "42") (pinfunction "~{2RE}_42") (pintype "input"))
      (node (ref "IC21") (pin "5") (pinfunction "2DE_5") (pintype "input"))
      (node (ref "IC21") (pin "8") (pinfunction "3DE_8") (pintype "input"))
      (node (ref "IC7") (pin "3") (pinfunction "C_3") (pintype "input"))
      (node (ref "R54") (pin "1") (pinfunction "1_1") (pintype "passive"))
      (node (ref "SW9") (pin "1") (pinfunction "1_1") (pintype "passive"))
    )
    (net (code "2") (name "/DIR_CTRL2") (class "Default")
      (node (ref "IC13") (pin "10") (pinfunction "P5_10") (pintype "bidirectional"))
      (node (ref "IC13") (pin "11") (pinfunction "P6_11") (pintype "bidirectional"))
      (node (ref "IC13") (pin "12") (pinfunction "P7_12") (pintype "bidirectional"))
      (node (ref "IC13") (pin "9") (pinfunction "P4_9") (pintype "bidirectional"))
      (node (ref "IC14") (pin "3") (pinfunction "C_3") (pintype "input"))
      (node (ref "IC9") (pin "1") (pinfunction "1DE_1") (pintype "input"))
      (node (ref "IC9") (pin "12") (pinfunction "4DE_12") (pintype "input"))
      (node (ref "IC9") (pin "19") (pinfunction "~{3RE}_19") (pintype "input"))
      (node (ref "IC9") (pin "21") (pinfunction "~{4RE}_21") (pintype "input"))
      (node (ref "IC9") (pin "40") (pinfunction "~{1RE}_40") (pintype "input"))
      (node (ref "IC9") (pin "42") (pinfunction "~{2RE}_42") (pintype "input"))
      (node (ref "IC9") (pin "5") (pinfunction "2DE_5") (pintype "input"))
      (node (ref "IC9") (pin "8") (pinfunction "3DE_8") (pintype "input"))
      (node (ref "R55") (pin "1") (pinfunction "1_1") (pintype "passive"))
      (node (ref "SW9") (pin "2") (pinfunction "2_2") (pintype "passive"))
    )
    (net (code "3") (name "/I2C_SCL") (class "Default")
      (node (ref "B8") (pin "1") (pinfunction "1_1") (pintype "bidirectional"))
      (node (ref "D2") (pin "2") (pinfunction "I/O1_2") (pintype "bidirectional"))
      (node (ref "IC13") (pin "14") (pinfunction "SCL_14") (pintype "input"))
      (node (ref "IC32") (pin "1") (pinfunction "SCL_1") (pintype "input"))
      (node (ref "J37") (pin "27") (pinfunction "27_27") (pintype "bidirectional"))
    )
    (net (code "4") (name "/I2C_SDA") (class "Default")
      (node (ref "B7") (pin "1") (pinfunction "1_1") (pintype "bidirectional"))
      (node (ref "D2") (pin "3") (pinfunction "I/O2_3") (pintype "bidirectional"))
      (node (ref "IC13") (pin "15") (pinfunction "SDA_15") (pintype "bidirectional"))
      (node (ref "IC32") (pin "3") (pinfunction "SDA_3") (pintype "bidirectional"))
      (node (ref "J37") (pin "26") (pinfunction "26_26") (pintype "bidirectional"))
    )
    (net (code "5") (name "/IO0") (class "Default")
      (node (ref "D1") (pin "2") (pinfunction "I/O1_2") (pintype "bidirectional"))
      (node (ref "J1") (pin "4") (pinfunction "4_4") (pintype "bidirectional"))
      (node (ref "R13") (pin "1") (pinfunction "1_1") (pintype "passive"))
      (node (ref "R139") (pin "2") (pinfunction "2_2") (pintype "passive"))
    )
    (net (code "6") (name "/IO1") (class "Default")
      (node (ref "D1") (pin "3") (pinfunction "I/O2_3") (pintype "bidirectional"))
      (node (ref "J1") (pin "2") (pinfunction "2_2") (pintype "bidirectional"))
      (node (ref "R14") (pin "1") (pinfunction "1_1") (pintype "passive"))
      (node (ref "R142") (pin "2") (pinfunction "2_2") (pintype "passive"))
    )
    (net (code "7") (name "/IO2") (class "Default")
      (node (ref "D3") (pin "2") (pinfunction "I/O1_2") (pintype "bidirectional"))
      (node (ref "J2") (pin "4") (pinfunction "4_4") (pintype "bidirectional"))
      (node (ref "R145") (pin "2") (pinfunction "2_2") (pintype "passive"))
      (node (ref "R15") (pin "1") (pinfunction "1_1") (pintype "passive"))
    )
    (net (code "8") (name "/IO3") (class "Default")
      (node (ref "D3") (pin "3") (pinfunction "I/O2_3") (pintype "bidirectional"))
      (node (ref "J2") (pin "2") (pinfunction "2_2") (pintype "bidirectional"))
      (node (ref "R148") (pin "2") (pinfunction "2_2") (pintype "passive"))
      (node (ref "R16") (pin "1") (pinfunction "1_1") (pintype "passive"))
    )
    (net (code "9") (name "/IO4") (class "Default")
      (node (ref "D4") (pin "2") (pinfunction "I/O1_2") (pintype "bidirectional"))
      (node (ref "J4") (pin "4") (pinfunction "4_4") (pintype "bidirectional"))
      (node (ref "R158") (pin "2") (pinfunction "2_2") (pintype "passive"))
      (node (ref "R20") (pin "1") (pinfunction "1_1") (pintype "passive"))
    )
    (net (code "10") (name "/IO5") (class "Default")
      (node (ref "D4") (pin "3") (pinfunction "I/O2_3") (pintype "bidirectional"))
      (node (ref "J4") (pin "2") (pinfunction "2_2") (pintype "bidirectional"))
      (node (ref "R161") (pin "2") (pinfunction "2_2") (pintype "passive"))
      (node (ref "R21") (pin "1") (pinfunction "1_1") (pintype "passive"))
    )
    (net (code "11") (name "/IO6") (class "Default")
      (node (ref "D5") (pin "2") (pinfunction "I/O1_2") (pintype "bidirectional"))
      (node (ref "J3") (pin "4") (pinfunction "4_4") (pintype "bidirectional"))
      (node (ref "R164") (pin "2") (pinfunction "2_2") (pintype "passive"))
      (node (ref "R22") (pin "1") (pinfunction "1_1") (pintype "passive"))
    )
    (net (code "12") (name "/IO7") (class "Default")
      (node (ref "D5") (pin "3") (pinfunction "I/O2_3") (pintype "bidirectional"))
      (node (ref "J3") (pin "2") (pinfunction "2_2") (pintype "bidirectional"))
      (node (ref "R168") (pin "2") (pinfunction "2_2") (pintype "passive"))
      (node (ref "R23") (pin "1") (pinfunction "1_1") (pintype "passive"))
    )
    (net (code "13") (name "/LED0") (class "Default")
      (node (ref "LD2") (pin "2") (pinfunction "A_2") (pintype "passive"))
      (node (ref "R1") (pin "2") (pinfunction "2_2") (pintype "passive"))
    )
    (net (code "14") (name "/LED1") (class "Default")
      (node (ref "LD2") (pin "4") (pinfunction "A_4") (pintype "passive"))
      (node (ref "R2") (pin "2") (pinfunction "2_2") (pintype "passive"))
    )
    (net (code "15") (name "/LED2") (class "Default")
      (node (ref "LD1") (pin "2") (pinfunction "A_2") (pintype "passive"))
      (node (ref "R3") (pin "2") (pinfunction "2_2") (pintype "passive"))
    )
    (net (code "16") (name "/LED3") (class "Default")
      (node (ref "LD1") (pin "4") (pinfunction "A_4") (pintype "passive"))
      (node (ref "R4") (pin "2") (pinfunction "2_2") (pintype "passive"))
    )
    (net (code "17") (name "/LED4") (class "Default")
      (node (ref "LD8") (pin "2") (pinfunction "A_2") (pintype "passive"))
      (node (ref "R5") (pin "2") (pinfunction "2_2") (pintype "passive"))
    )
    (net (code "18") (name "/LED5") (class "Default")
      (node (ref "LD8") (pin "4") (pinfunction "A_4") (pintype "passive"))
      (node (ref "R7") (pin "2") (pinfunction "2_2") (pintype "passive"))
    )
    (net (code "19") (name "/LED6") (class "Default")
      (node (ref "LD3") (pin "2") (pinfunction "A_2") (pintype "passive"))
      (node (ref "R9") (pin "2") (pinfunction "2_2") (pintype "passive"))
    )
    (net (code "20") (name "/LED7") (class "Default")
      (node (ref "LD3") (pin "4") (pinfunction "A_4") (pintype "passive"))
      (node (ref "R11") (pin "2") (pinfunction "2_2") (pintype "passive"))
    )
    (net (code "21") (name "/LED_OUT1") (class "Default")
      (node (ref "IC7") (pin "4") (pinfunction "E_4") (pintype "open_emitter"))
      (node (ref "LD5") (pin "2") (pinfunction "A_2") (pintype "passive"))
      (node (ref "R17") (pin "1") (pinfunction "1_1") (pintype "passive"))
      (node (ref "R45") (pin "2") (pinfunction "2_2") (pintype "passive"))
      (node (ref "R48") (pin "2") (pinfunction "2_2") (pintype "passive"))
      (node (ref "T27") (pin "1") (pinfunction "G_1") (pintype "passive"))
    )
    (net (code "22") (name "/LED_OUT2") (class "Default")
      (node (ref "IC14") (pin "4") (pinfunction "E_4") (pintype "open_emitter"))
      (node (ref "LD6") (pin "2") (pinfunction "A_2") (pintype "passive"))
      (node (ref "R24") (pin "1") (pinfunction "1_1") (pintype "passive"))
      (node (ref "R50") (pin "2") (pinfunction "2_2") (pintype "passive"))
      (node (ref "R53") (pin "2") (pinfunction "2_2") (pintype "passive"))
      (node (ref "T29") (pin "1") (pinfunction "G_1") (pintype "passive"))
    )
    (net (code "23") (name "/LVDS0_N") (class "Default")
      (node (ref "IC21") (pin "48") (pinfunction "1B_48") (pintype "bidirectional"))
      (node (ref "J37") (pin "3") (pinfunction "3_3") (pintype "bidirectional"))
      (node (ref "R141") (pin "2") (pinfunction "2_2") (pintype "passive"))
    )
    (net (code "24") (name "/LVDS0_P") (class "Default")
      (node (ref "IC21") (pin "47") (pinfunction "1A_47") (pintype "bidirectional"))
      (node (ref "J37") (pin "2") (pinfunction "2_2") (pintype "bidirectional"))
      (node (ref "R141") (pin "1") (pinfunction "1_1") (pintype "passive"))
    )
    (net (code "25") (name "/LVDS1_N") (class "Default")
      (node (ref "IC21") (pin "4") (pinfunction "2B_4") (pintype "bidirectional"))
      (node (ref "J37") (pin "6") (pinfunction "6_6") (pintype "bidirectional"))
      (node (ref "R144") (pin "2") (pinfunction "2_2") (pintype "passive"))
    )
    (net (code "26") (name "/LVDS1_P") (class "Default")
      (node (ref "IC21") (pin "3") (pinfunction "2A_3") (pintype "bidirectional"))
      (node (ref "J37") (pin "5") (pinfunction "5_5") (pintype "bidirectional"))
      (node (ref "R144") (pin "1") (pinfunction "1_1") (pintype "passive"))
    )
    (net (code "27") (name "/LVDS2_N") (class "Default")
      (node (ref "IC21") (pin "10") (pinfunction "3B_10") (pintype "bidirectional"))
      (node (ref "J37") (pin "9") (pinfunction "9_9") (pintype "bidirectional"))
      (node (ref "R147") (pin "2") (pinfunction "2_2") (pintype "passive"))
    )
    (net (code "28") (name "/LVDS2_P") (class "Default")
      (node (ref "IC21") (pin "9") (pinfunction "3A_9") (pintype "bidirectional"))
      (node (ref "J37") (pin "8") (pinfunction "8_8") (pintype "bidirectional"))
      (node (ref "R147") (pin "1") (pinfunction "1_1") (pintype "passive"))
    )
    (net (code "29") (name "/LVDS3_N") (class "Default")
      (node (ref "IC21") (pin "14") (pinfunction "4B_14") (pintype "bidirectional"))
      (node (ref "J37") (pin "12") (pinfunction "12_12") (pintype "bidirectional"))
      (node (ref "R151") (pin "2") (pinfunction "2_2") (pintype "passive"))
    )
    (net (code "30") (name "/LVDS3_P") (class "Default")
      (node (ref "IC21") (pin "13") (pinfunction "4A_13") (pintype "bidirectional"))
      (node (ref "J37") (pin "11") (pinfunction "11_11") (pintype "bidirectional"))
      (node (ref "R151") (pin "1") (pinfunction "1_1") (pintype "passive"))
    )
    (net (code "31") (name "/LVDS4_N") (class "Default")
      (node (ref "IC9") (pin "48") (pinfunction "1B_48") (pintype "bidirectional"))
      (node (ref "J37") (pin "15") (pinfunction "15_15") (pintype "bidirectional"))
      (node (ref "R160") (pin "2") (pinfunction "2_2") (pintype "passive"))
    )
    (net (code "32") (name "/LVDS4_P") (class "Default")
      (node (ref "IC9") (pin "47") (pinfunction "1A_47") (pintype "bidirectional"))
      (node (ref "J37") (pin "14") (pinfunction "14_14") (pintype "bidirectional"))
      (node (ref "R160") (pin "1") (pinfunction "1_1") (pintype "passive"))
    )
    (net (code "33") (name "/LVDS5_N") (class "Default")
      (node (ref "IC9") (pin "4") (pinfunction "2B_4") (pintype "bidirectional"))
      (node (ref "J37") (pin "18") (pinfunction "18_18") (pintype "bidirectional"))
      (node (ref "R163") (pin "2") (pinfunction "2_2") (pintype "passive"))
    )
    (net (code "34") (name "/LVDS5_P") (class "Default")
      (node (ref "IC9") (pin "3") (pinfunction "2A_3") (pintype "bidirectional"))
      (node (ref "J37") (pin "17") (pinfunction "17_17") (pintype "bidirectional"))
      (node (ref "R163") (pin "1") (pinfunction "1_1") (pintype "passive"))
    )
    (net (code "35") (name "/LVDS6_N") (class "Default")
      (node (ref "IC9") (pin "10") (pinfunction "3B_10") (pintype "bidirectional"))
      (node (ref "J37") (pin "21") (pinfunction "21_21") (pintype "bidirectional"))
      (node (ref "R166") (pin "2") (pinfunction "2_2") (pintype "passive"))
    )
    (net (code "36") (name "/LVDS6_P") (class "Default")
      (node (ref "IC9") (pin "9") (pinfunction "3A_9") (pintype "bidirectional"))
      (node (ref "J37") (pin "20") (pinfunction "20_20") (pintype "bidirectional"))
      (node (ref "R166") (pin "1") (pinfunction "1_1") (pintype "passive"))
    )
    (net (code "37") (name "/LVDS7_N") (class "Default")
      (node (ref "IC9") (pin "14") (pinfunction "4B_14") (pintype "bidirectional"))
      (node (ref "J37") (pin "24") (pinfunction "24_24") (pintype "bidirectional"))
      (node (ref "R170") (pin "2") (pinfunction "2_2") (pintype "passive"))
    )
    (net (code "38") (name "/LVDS7_P") (class "Default")
      (node (ref "IC9") (pin "13") (pinfunction "4A_13") (pintype "bidirectional"))
      (node (ref "J37") (pin "23") (pinfunction "23_23") (pintype "bidirectional"))
      (node (ref "R170") (pin "1") (pinfunction "1_1") (pintype "passive"))
    )
    (net (code "39") (name "/TERM_IO0") (class "Default")
      (node (ref "C10") (pin "2") (pinfunction "2_2") (pintype "passive"))
      (node (ref "R1") (pin "1") (pinfunction "1_1") (pintype "passive"))
      (node (ref "R39") (pin "2") (pinfunction "2_2") (pintype "passive"))
      (node (ref "SW1") (pin "8") (pinfunction "8_8") (pintype "passive"))
      (node (ref "T1") (pin "1") (pinfunction "G_1") (pintype "passive"))
    )
    (net (code "40") (name "/TERM_IO1") (class "Default")
      (node (ref "C9") (pin "2") (pinfunction "2_2") (pintype "passive"))
      (node (ref "R2") (pin "1") (pinfunction "1_1") (pintype "passive"))
      (node (ref "R38") (pin "2") (pinfunction "2_2") (pintype "passive"))
      (node (ref "SW1") (pin "7") (pinfunction "7_7") (pintype "passive"))
      (node (ref "T2") (pin "1") (pinfunction "G_1") (pintype "passive"))
    )
    (net (code "41") (name "/TERM_IO2") (class "Default")
      (node (ref "C8") (pin "2") (pinfunction "2_2") (pintype "passive"))
      (node (ref "R3") (pin "1") (pinfunction "1_1") (pintype "passive"))
      (node (ref "R37") (pin "2") (pinfunction "2_2") (pintype "passive"))
      (node (ref "SW1") (pin "6") (pinfunction "6_6") (pintype "passive"))
      (node (ref "T3") (pin "1") (pinfunction "G_1") (pintype "passive"))
    )
    (net (code "42") (name "/TERM_IO3") (class "Default")
      (node (ref "C7") (pin "2") (pinfunction "2_2") (pintype "passive"))
      (node (ref "R36") (pin "2") (pinfunction "2_2") (pintype "passive"))
      (node (ref "R4") (pin "1") (pinfunction "1_1") (pintype "passive"))
      (node (ref "SW1") (pin "5") (pinfunction "5_5") (pintype "passive"))
      (node (ref "T4") (pin "1") (pinfunction "G_1") (pintype "passive"))
    )
    (net (code "43") (name "/TERM_IO4") (class "Default")
      (node (ref "C25") (pin "2") (pinfunction "2_2") (pintype "passive"))
      (node (ref "R43") (pin "2") (pinfunction "2_2") (pintype "passive"))
      (node (ref "R5") (pin "1") (pinfunction "1_1") (pintype "passive"))
      (node (ref "SW2") (pin "8") (pinfunction "8_8") (pintype "passive"))
      (node (ref "T5") (pin "1") (pinfunction "G_1") (pintype "passive"))
    )
    (net (code "44") (name "/TERM_IO5") (class "Default")
      (node (ref "C13") (pin "2") (pinfunction "2_2") (pintype "passive"))
      (node (ref "R42") (pin "2") (pinfunction "2_2") (pintype "passive"))
      (node (ref "R7") (pin "1") (pinfunction "1_1") (pintype "passive"))
      (node (ref "SW2") (pin "7") (pinfunction "7_7") (pintype "passive"))
      (node (ref "T6") (pin "1") (pinfunction "G_1") (pintype "passive"))
    )
    (net (code "45") (name "/TERM_IO6") (class "Default")
      (node (ref "C12") (pin "2") (pinfunction "2_2") (pintype "passive"))
      (node (ref "R41") (pin "2") (pinfunction "2_2") (pintype "passive"))
      (node (ref "R9") (pin "1") (pinfunction "1_1") (pintype "passive"))
      (node (ref "SW2") (pin "6") (pinfunction "6_6") (pintype "passive"))
      (node (ref "T7") (pin "1") (pinfunction "G_1") (pintype "passive"))
    )
    (net (code "46") (name "/TERM_IO7") (class "Default")
      (node (ref "C11") (pin "2") (pinfunction "2_2") (pintype "passive"))
      (node (ref "R11") (pin "1") (pinfunction "1_1") (pintype "passive"))
      (node (ref "R40") (pin "2") (pinfunction "2_2") (pintype "passive"))
      (node (ref "SW2") (pin "5") (pinfunction "5_5") (pintype "passive"))
      (node (ref "T8") (pin "1") (pinfunction "G_1") (pintype "passive"))
    )
    (net (code "47") (name "GND") (class "Default")
      (node (ref "B1") (pin "1") (pinfunction "1_1") (pintype "bidirectional"))
      (node (ref "B2") (pin "1") (pinfunction "1_1") (pintype "bidirectional"))
      (node (ref "B4") (pin "1") (pinfunction "1_1") (pintype "bidirectional"))
      (node (ref "C37") (pin "1") (pinfunction "1_1") (pintype "passive"))
      (node (ref "C38") (pin "1") (pinfunction "1_1") (pintype "passive"))
      (node (ref "C5") (pin "2") (pinfunction "2_2") (pintype "passive"))
      (node (ref "C6") (pin "2") (pinfunction "2_2") (pintype "passive"))
      (node (ref "D2") (pin "1") (pinfunction "GND_1") (pintype "power_in"))
      (node (ref "IC10") (pin "9") (pinfunction "GND2_9") (pintype "power_in"))
      (node (ref "IC11") (pin "2") (pinfunction "A1/G_2") (pintype "input"))
      (node (ref "IC11") (pin "8") (pinfunction "GND1_8") (pintype "power_in"))
      (node (ref "IC13") (pin "1") (pinfunction "A0_1") (pintype "input"))
      (node (ref "IC13") (pin "8") (pinfunction "GND_8") (pintype "power_in"))
      (node (ref "IC21") (pin "18") (pinfunction "GND_18") (pintype "power_in"))
      (node (ref "IC21") (pin "23") (pinfunction "GND_23") (pintype "power_in"))
      (node (ref "IC21") (pin "27") (pinfunction "GND_27") (pintype "power_in"))
      (node (ref "IC21") (pin "31") (pinfunction "GND_31") (pintype "power_in"))
      (node (ref "IC21") (pin "34") (pinfunction "GND_34") (pintype "power_in"))
      (node (ref "IC21") (pin "38") (pinfunction "GND_38") (pintype "power_in"))
      (node (ref "IC21") (pin "43") (pinfunction "GND_43") (pintype "power_in"))
      (node (ref "IC21") (pin "49") (pinfunction "EP_49") (pintype "power_in"))
      (node (ref "IC21") (pin "6") (pinfunction "GND_6") (pintype "power_in"))
      (node (ref "IC21") (pin "7") (pinfunction "GND_7") (pintype "power_in"))
      (node (ref "IC32") (pin "2") (pinfunction "VSS_2") (pintype "power_in"))
      (node (ref "IC5") (pin "9") (pinfunction "GND2_9") (pintype "power_in"))
      (node (ref "IC6") (pin "2") (pinfunction "A1/G_2") (pintype "input"))
      (node (ref "IC6") (pin "8") (pinfunction "GND1_8") (pintype "power_in"))
      (node (ref "IC9") (pin "18") (pinfunction "GND_18") (pintype "power_in"))
      (node (ref "IC9") (pin "23") (pinfunction "GND_23") (pintype "power_in"))
      (node (ref "IC9") (pin "27") (pinfunction "GND_27") (pintype "power_in"))
      (node (ref "IC9") (pin "31") (pinfunction "GND_31") (pintype "power_in"))
      (node (ref "IC9") (pin "34") (pinfunction "GND_34") (pintype "power_in"))
      (node (ref "IC9") (pin "38") (pinfunction "GND_38") (pintype "power_in"))
      (node (ref "IC9") (pin "43") (pinfunction "GND_43") (pintype "power_in"))
      (node (ref "IC9") (pin "49") (pinfunction "EP_49") (pintype "power_in"))
      (node (ref "IC9") (pin "6") (pinfunction "GND_6") (pintype "power_in"))
      (node (ref "IC9") (pin "7") (pinfunction "GND_7") (pintype "power_in"))
      (node (ref "J37") (pin "1") (pinfunction "1_1") (pintype "bidirectional"))
      (node (ref "J37") (pin "10") (pinfunction "10_10") (pintype "bidirectional"))
      (node (ref "J37") (pin "13") (pinfunction "13_13") (pintype "bidirectional"))
      (node (ref "J37") (pin "16") (pinfunction "16_16") (pintype "bidirectional"))
      (node (ref "J37") (pin "19") (pinfunction "19_19") (pintype "bidirectional"))
      (node (ref "J37") (pin "22") (pinfunction "22_22") (pintype "bidirectional"))
      (node (ref "J37") (pin "25") (pinfunction "25_25") (pintype "bidirectional"))
      (node (ref "J37") (pin "4") (pinfunction "4_4") (pintype "bidirectional"))
      (node (ref "J37") (pin "7") (pinfunction "7_7") (pintype "bidirectional"))
      (node (ref "R138") (pin "2") (pinfunction "2_2") (pintype "passive"))
      (node (ref "R152") (pin "2") (pinfunction "2_2") (pintype "passive"))
      (node (ref "R157") (pin "2") (pinfunction "2_2") (pintype "passive"))
      (node (ref "R171") (pin "2") (pinfunction "2_2") (pintype "passive"))
      (node (ref "R34") (pin "1") (pinfunction "1_1") (pintype "passive"))
      (node (ref "R35") (pin "1") (pinfunction "1_1") (pintype "passive"))
      (node (ref "R46") (pin "2") (pinfunction "2_2") (pintype "passive"))
      (node (ref "R51") (pin "2") (pinfunction "2_2") (pintype "passive"))
      (node (ref "SW9") (pin "3") (pinfunction "3_3") (pintype "passive"))
      (node (ref "SW9") (pin "4") (pinfunction "4_4") (pintype "passive"))
    )
    (net (code "48") (name "GND_ISO1") (class "Default")
      (node (ref "C10") (pin "1") (pinfunction "1_1") (pintype "passive"))
      (node (ref "C7") (pin "1") (pinfunction "1_1") (pintype "passive"))
      (node (ref "C8") (pin "1") (pinfunction "1_1") (pintype "passive"))
      (node (ref "C9") (pin "1") (pinfunction "1_1") (pintype "passive"))
      (node (ref "D1") (pin "1") (pinfunction "GND_1") (pintype "power_in"))
      (node (ref "D3") (pin "1") (pinfunction "GND_1") (pintype "power_in"))
      (node (ref "IC29") (pin "11") (pinfunction "GND_11") (pintype "power_in"))
      (node (ref "IC29") (pin "2") (pinfunction "GND_2") (pintype "power_in"))
      (node (ref "IC29") (pin "5") (pinfunction "GND_5") (pintype "power_in"))
      (node (ref "IC29") (pin "8") (pinfunction "GND_8") (pintype "power_in"))
      (node (ref "IC3") (pin "1") (pinfunction "VSS_1") (pintype "power_in"))
      (node (ref "IC5") (pin "2") (pinfunction "A1/G_2") (pintype "input"))
      (node (ref "IC5") (pin "8") (pinfunction "GND1_8") (pintype "power_in"))
      (node (ref "IC6") (pin "9") (pinfunction "GND2_9") (pintype "power_in"))
      (node (ref "J1") (pin "1") (pinfunction "1_1") (pintype "bidirectional"))
      (node (ref "J1") (pin "3") (pinfunction "3_3") (pintype "bidirectional"))
      (node (ref "J2") (pin "1") (pinfunction "1_1") (pintype "bidirectional"))
      (node (ref "J2") (pin "3") (pinfunction "3_3") (pintype "bidirectional"))
      (node (ref "LD1") (pin "1") (pinfunction "C_1") (pintype "passive"))
      (node (ref "LD1") (pin "3") (pinfunction "C_3") (pintype "passive"))
      (node (ref "LD2") (pin "1") (pinfunction "C_1") (pintype "passive"))
      (node (ref "LD2") (pin "3") (pinfunction "C_3") (pintype "passive"))
      (node (ref "R12") (pin "1") (pinfunction "1_1") (pintype "passive"))
      (node (ref "R140") (pin "1") (pinfunction "1_1") (pintype "passive"))
      (node (ref "R143") (pin "1") (pinfunction "1_1") (pintype "passive"))
      (node (ref "R146") (pin "1") (pinfunction "1_1") (pintype "passive"))
      (node (ref "R149") (pin "1") (pinfunction "1_1") (pintype "passive"))
      (node (ref "R36") (pin "1") (pinfunction "1_1") (pintype "passive"))
      (node (ref "R37") (pin "1") (pinfunction "1_1") (pintype "passive"))
      (node (ref "R38") (pin "1") (pinfunction "1_1") (pintype "passive"))
      (node (ref "R39") (pin "1") (pinfunction "1_1") (pintype "passive"))
      (node (ref "R44") (pin "2") (pinfunction "2_2") (pintype "passive"))
      (node (ref "R47") (pin "1") (pinfunction "1_1") (pintype "passive"))
      (node (ref "R48") (pin "1") (pinfunction "1_1") (pintype "passive"))
      (node (ref "T1") (pin "2") (pinfunction "S_2") (pintype "passive"))
      (node (ref "T2") (pin "2") (pinfunction "S_2") (pintype "passive"))
      (node (ref "T27") (pin "2") (pinfunction "S_2") (pintype "passive"))
      (node (ref "T3") (pin "2") (pinfunction "S_2") (pintype "passive"))
      (node (ref "T4") (pin "2") (pinfunction "S_2") (pintype "passive"))
    )
    (net (code "49") (name "GND_ISO2") (class "Default")
      (node (ref "C11") (pin "1") (pinfunction "1_1") (pintype "passive"))
      (node (ref "C12") (pin "1") (pinfunction "1_1") (pintype "passive"))
      (node (ref "C13") (pin "1") (pinfunction "1_1") (pintype "passive"))
      (node (ref "C25") (pin "1") (pinfunction "1_1") (pintype "passive"))
      (node (ref "D4") (pin "1") (pinfunction "GND_1") (pintype "power_in"))
      (node (ref "D5") (pin "1") (pinfunction "GND_1") (pintype "power_in"))
      (node (ref "IC10") (pin "2") (pinfunction "A1/G_2") (pintype "input"))
      (node (ref "IC10") (pin "8") (pinfunction "GND1_8") (pintype "power_in"))
      (node (ref "IC11") (pin "9") (pinfunction "GND2_9") (pintype "power_in"))
      (node (ref "IC4") (pin "1") (pinfunction "VSS_1") (pintype "power_in"))
      (node (ref "IC8") (pin "11") (pinfunction "GND_11") (pintype "power_in"))
      (node (ref "IC8") (pin "2") (pinfunction "GND_2") (pintype "power_in"))
      (node (ref "IC8") (pin "5") (pinfunction "GND_5") (pintype "power_in"))
      (node (ref "IC8") (pin "8") (pinfunction "GND_8") (pintype "power_in"))
      (node (ref "J3") (pin "1") (pinfunction "1_1") (pintype "bidirectional"))
      (node (ref "J3") (pin "3") (pinfunction "3_3") (pintype "bidirectional"))
      (node (ref "J4") (pin "1") (pinfunction "1_1") (pintype "bidirectional"))
      (node (ref "J4") (pin "3") (pinfunction "3_3") (pintype "bidirectional"))
      (node (ref "LD3") (pin "1") (pinfunction "C_1") (pintype "passive"))
      (node (ref "LD3") (pin "3") (pinfunction "C_3") (pintype "passive"))
      (node (ref "LD8") (pin "1") (pinfunction "C_1") (pintype "passive"))
      (node (ref "LD8") (pin "3") (pinfunction "C_3") (pintype "passive"))
      (node (ref "R159") (pin "1") (pinfunction "1_1") (pintype "passive"))
      (node (ref "R162") (pin "1") (pinfunction "1_1") (pintype "passive"))
      (node (ref "R165") (pin "1") (pinfunction "1_1") (pintype "passive"))
      (node (ref "R169") (pin "1") (pinfunction "1_1") (pintype "passive"))
      (node (ref "R19") (pin "1") (pinfunction "1_1") (pintype "passive"))
      (node (ref "R40") (pin "1") (pinfunction "1_1") (pintype "passive"))
      (node (ref "R41") (pin "1") (pinfunction "1_1") (pintype "passive"))
      (node (ref "R42") (pin "1") (pinfunction "1_1") (pintype "passive"))
      (node (ref "R43") (pin "1") (pinfunction "1_1") (pintype "passive"))
      (node (ref "R49") (pin "2") (pinfunction "2_2") (pintype "passive"))
      (node (ref "R52") (pin "2") (pinfunction "2_2") (pintype "passive"))
      (node (ref "R53") (pin "1") (pinfunction "1_1") (pintype "passive"))
      (node (ref "T29") (pin "2") (pinfunction "S_2") (pintype "passive"))
      (node (ref "T5") (pin "2") (pinfunction "S_2") (pintype "passive"))
      (node (ref "T6") (pin "2") (pinfunction "S_2") (pintype "passive"))
      (node (ref "T7") (pin "2") (pinfunction "S_2") (pintype "passive"))
      (node (ref "T8") (pin "2") (pinfunction "S_2") (pintype "passive"))
    )
    (net (code "50") (name "Net-(B13-Pad1)") (class "Default")
      (node (ref "B13") (pin "1") (pinfunction "1_1") (pintype "bidirectional"))
      (node (ref "C5") (pin "1") (pinfunction "1_1") (pintype "passive"))
      (node (ref "R34") (pin "2") (pinfunction "2_2") (pintype "passive"))
    )
    (net (code "51") (name "Net-(B14-Pad1)") (class "Default")
      (node (ref "B14") (pin "1") (pinfunction "1_1") (pintype "bidirectional"))
      (node (ref "C6") (pin "1") (pinfunction "1_1") (pintype "passive"))
      (node (ref "R35") (pin "2") (pinfunction "2_2") (pintype "passive"))
    )
    (net (code "52") (name "Net-(IC4-RST)") (class "Default")
      (node (ref "IC4") (pin "2") (pinfunction "RST_2") (pintype "output"))
      (node (ref "IC8") (pin "13") (pinfunction "OE_13") (pintype "input"))
      (node (ref "R19") (pin "2") (pinfunction "2_2") (pintype "passive"))
    )
    (net (code "53") (name "Net-(IC5-A2)") (class "Default")
      (node (ref "IC5") (pin "3") (pinfunction "A2_3") (pintype "input"))
      (node (ref "IC6") (pin "14") (pinfunction "B2_14") (pintype "output"))
      (node (ref "R26") (pin "2") (pinfunction "2_2") (pintype "passive"))
    )
    (net (code "54") (name "Net-(IC5-A3)") (class "Default")
      (node (ref "IC5") (pin "4") (pinfunction "A3_4") (pintype "input"))
      (node (ref "IC6") (pin "13") (pinfunction "B3_13") (pintype "output"))
      (node (ref "R27") (pin "2") (pinfunction "2_2") (pintype "passive"))
    )
    (net (code "55") (name "Net-(IC5-A4)") (class "Default")
      (node (ref "IC5") (pin "5") (pinfunction "A4_5") (pintype "input"))
      (node (ref "IC6") (pin "12") (pinfunction "B4_12") (pintype "output"))
      (node (ref "R28") (pin "2") (pinfunction "2_2") (pintype "passive"))
    )
    (net (code "56") (name "Net-(IC5-A5)") (class "Default")
      (node (ref "IC5") (pin "6") (pinfunction "A5_6") (pintype "input"))
      (node (ref "IC6") (pin "11") (pinfunction "B5_11") (pintype "output"))
      (node (ref "R29") (pin "2") (pinfunction "2_2") (pintype "passive"))
    )
    (net (code "57") (name "Net-(IC5-B1{slash}G)") (class "Default")
      (node (ref "IC5") (pin "15") (pinfunction "B1/G_15") (pintype "output"))
      (node (ref "R46") (pin "1") (pinfunction "1_1") (pintype "passive"))
    )
    (net (code "58") (name "Net-(IC6-B1{slash}G)") (class "Default")
      (node (ref "IC6") (pin "15") (pinfunction "B1/G_15") (pintype "output"))
      (node (ref "R47") (pin "2") (pinfunction "2_2") (pintype "passive"))
    )
    (net (code "59") (name "Net-(IC6-EN2)") (class "Default")
      (node (ref "IC6") (pin "10") (pinfunction "EN2_10") (pintype "passive"))
      (node (ref "R17") (pin "2") (pinfunction "2_2") (pintype "passive"))
    )
    (net (code "60") (name "Net-(IC7-A)") (class "Default")
      (node (ref "IC7") (pin "1") (pinfunction "A_1") (pintype "input"))
      (node (ref "R56") (pin "1") (pinfunction "1_1") (pintype "passive"))
      (node (ref "R57") (pin "1") (pinfunction "1_1") (pintype "passive"))
    )
    (net (code "61") (name "Net-(IC8-A1)") (class "Default")
      (node (ref "IC8") (pin "1") (pinfunction "A1_1") (pintype "bidirectional"))
      (node (ref "IC8") (pin "3") (pinfunction "A2_3") (pintype "bidirectional"))
      (node (ref "R169") (pin "2") (pinfunction "2_2") (pintype "passive"))
      (node (ref "R23") (pin "2") (pinfunction "2_2") (pintype "passive"))
    )
    (net (code "62") (name "Net-(IC8-A3)") (class "Default")
      (node (ref "IC8") (pin "4") (pinfunction "A3_4") (pintype "bidirectional"))
      (node (ref "IC8") (pin "6") (pinfunction "A4_6") (pintype "bidirectional"))
      (node (ref "R165") (pin "2") (pinfunction "2_2") (pintype "passive"))
      (node (ref "R22") (pin "2") (pinfunction "2_2") (pintype "passive"))
    )
    (net (code "63") (name "Net-(IC8-A5)") (class "Default")
      (node (ref "IC8") (pin "7") (pinfunction "A5_7") (pintype "bidirectional"))
      (node (ref "IC8") (pin "9") (pinfunction "A6_9") (pintype "bidirectional"))
      (node (ref "R162") (pin "2") (pinfunction "2_2") (pintype "passive"))
      (node (ref "R21") (pin "2") (pinfunction "2_2") (pintype "passive"))
    )
    (net (code "64") (name "Net-(IC8-A7)") (class "Default")
      (node (ref "IC8") (pin "10") (pinfunction "A7_10") (pintype "bidirectional"))
      (node (ref "IC8") (pin "12") (pinfunction "A8_12") (pintype "bidirectional"))
      (node (ref "R159") (pin "2") (pinfunction "2_2") (pintype "passive"))
      (node (ref "R20") (pin "2") (pinfunction "2_2") (pintype "passive"))
    )
    (net (code "65") (name "Net-(IC8-B1)") (class "Default")
      (node (ref "IC8") (pin "22") (pinfunction "B2_22") (pintype "bidirectional"))
      (node (ref "IC8") (pin "23") (pinfunction "B1_23") (pintype "bidirectional"))
      (node (ref "R33") (pin "1") (pinfunction "1_1") (pintype "passive"))
    )
    (net (code "66") (name "Net-(IC8-B3)") (class "Default")
      (node (ref "IC8") (pin "19") (pinfunction "B4_19") (pintype "bidirectional"))
      (node (ref "IC8") (pin "20") (pinfunction "B3_20") (pintype "bidirectional"))
      (node (ref "R32") (pin "1") (pinfunction "1_1") (pintype "passive"))
    )
    (net (code "67") (name "Net-(IC8-B5)") (class "Default")
      (node (ref "IC8") (pin "17") (pinfunction "B6_17") (pintype "bidirectional"))
      (node (ref "IC8") (pin "18") (pinfunction "B5_18") (pintype "bidirectional"))
      (node (ref "R31") (pin "1") (pinfunction "1_1") (pintype "passive"))
    )
    (net (code "68") (name "Net-(IC8-B7)") (class "Default")
      (node (ref "IC8") (pin "14") (pinfunction "B8_14") (pintype "bidirectional"))
      (node (ref "IC8") (pin "15") (pinfunction "B7_15") (pintype "bidirectional"))
      (node (ref "R30") (pin "1") (pinfunction "1_1") (pintype "passive"))
    )
    (net (code "69") (name "Net-(IC8-DIR)") (class "Default")
      (node (ref "IC8") (pin "24") (pinfunction "DIR_24") (pintype "input"))
      (node (ref "R172") (pin "1") (pinfunction "1_1") (pintype "passive"))
      (node (ref "T29") (pin "3") (pinfunction "D_3") (pintype "passive"))
    )
    (net (code "70") (name "Net-(IC9-1FSEN)") (class "Default")
      (node (ref "IC9") (pin "20") (pinfunction "3FSEN_20") (pintype "input"))
      (node (ref "IC9") (pin "22") (pinfunction "4FSEN_22") (pintype "input"))
      (node (ref "IC9") (pin "39") (pinfunction "1FSEN_39") (pintype "input"))
      (node (ref "IC9") (pin "41") (pinfunction "2FSEN_41") (pintype "input"))
      (node (ref "R157") (pin "1") (pinfunction "1_1") (pintype "passive"))
      (node (ref "R171") (pin "1") (pinfunction "1_1") (pintype "passive"))
    )
    (net (code "71") (name "Net-(IC10-A2)") (class "Default")
      (node (ref "IC10") (pin "3") (pinfunction "A2_3") (pintype "input"))
      (node (ref "IC11") (pin "14") (pinfunction "B2_14") (pintype "output"))
      (node (ref "R30") (pin "2") (pinfunction "2_2") (pintype "passive"))
    )
    (net (code "72") (name "Net-(IC10-A3)") (class "Default")
      (node (ref "IC10") (pin "4") (pinfunction "A3_4") (pintype "input"))
      (node (ref "IC11") (pin "13") (pinfunction "B3_13") (pintype "output"))
      (node (ref "R31") (pin "2") (pinfunction "2_2") (pintype "passive"))
    )
    (net (code "73") (name "Net-(IC10-A4)") (class "Default")
      (node (ref "IC10") (pin "5") (pinfunction "A4_5") (pintype "input"))
      (node (ref "IC11") (pin "12") (pinfunction "B4_12") (pintype "output"))
      (node (ref "R32") (pin "2") (pinfunction "2_2") (pintype "passive"))
    )
    (net (code "74") (name "Net-(IC10-A5)") (class "Default")
      (node (ref "IC10") (pin "6") (pinfunction "A5_6") (pintype "input"))
      (node (ref "IC11") (pin "11") (pinfunction "B5_11") (pintype "output"))
      (node (ref "R33") (pin "2") (pinfunction "2_2") (pintype "passive"))
    )
    (net (code "75") (name "Net-(IC10-B1{slash}G)") (class "Default")
      (node (ref "IC10") (pin "15") (pinfunction "B1/G_15") (pintype "output"))
      (node (ref "R51") (pin "1") (pinfunction "1_1") (pintype "passive"))
    )
    (net (code "76") (name "Net-(IC10-B2)") (class "Default")
      (node (ref "IC10") (pin "14") (pinfunction "B2_14") (pintype "output"))
      (node (ref "IC9") (pin "35") (pinfunction "1D_35") (pintype "input"))
    )
    (net (code "77") (name "Net-(IC10-B3)") (class "Default")
      (node (ref "IC10") (pin "13") (pinfunction "B3_13") (pintype "output"))
      (node (ref "IC9") (pin "32") (pinfunction "2D_32") (pintype "input"))
    )
    (net (code "78") (name "Net-(IC10-B4)") (class "Default")
      (node (ref "IC10") (pin "12") (pinfunction "B4_12") (pintype "output"))
      (node (ref "IC9") (pin "28") (pinfunction "3D_28") (pintype "input"))
    )
    (net (code "79") (name "Net-(IC10-B5)") (class "Default")
      (node (ref "IC10") (pin "11") (pinfunction "B5_11") (pintype "output"))
      (node (ref "IC9") (pin "25") (pinfunction "4D_25") (pintype "input"))
    )
    (net (code "80") (name "Net-(IC11-A2)") (class "Default")
      (node (ref "IC11") (pin "3") (pinfunction "A2_3") (pintype "input"))
      (node (ref "IC9") (pin "36") (pinfunction "1R_36") (pintype "output"))
    )
    (net (code "81") (name "Net-(IC11-A3)") (class "Default")
      (node (ref "IC11") (pin "4") (pinfunction "A3_4") (pintype "input"))
      (node (ref "IC9") (pin "33") (pinfunction "2R_33") (pintype "output"))
    )
    (net (code "82") (name "Net-(IC11-A4)") (class "Default")
      (node (ref "IC11") (pin "5") (pinfunction "A4_5") (pintype "input"))
      (node (ref "IC9") (pin "29") (pinfunction "3R_29") (pintype "output"))
    )
    (net (code "83") (name "Net-(IC11-A5)") (class "Default")
      (node (ref "IC11") (pin "6") (pinfunction "A5_6") (pintype "input"))
      (node (ref "IC9") (pin "26") (pinfunction "4R_26") (pintype "output"))
    )
    (net (code "84") (name "Net-(IC11-B1{slash}G)") (class "Default")
      (node (ref "IC11") (pin "15") (pinfunction "B1/G_15") (pintype "output"))
      (node (ref "R52") (pin "1") (pinfunction "1_1") (pintype "passive"))
    )
    (net (code "85") (name "Net-(IC11-EN2)") (class "Default")
      (node (ref "IC11") (pin "10") (pinfunction "EN2_10") (pintype "passive"))
      (node (ref "R24") (pin "2") (pinfunction "2_2") (pintype "passive"))
    )
    (net (code "86") (name "Net-(IC14-A)") (class "Default")
      (node (ref "IC14") (pin "1") (pinfunction "A_1") (pintype "input"))
      (node (ref "R58") (pin "1") (pinfunction "1_1") (pintype "passive"))
      (node (ref "R59") (pin "1") (pinfunction "1_1") (pintype "passive"))
    )
    (net (code "87") (name "Net-(IC21-1D)") (class "Default")
      (node (ref "IC21") (pin "35") (pinfunction "1D_35") (pintype "input"))
      (node (ref "IC5") (pin "14") (pinfunction "B2_14") (pintype "output"))
    )
    (net (code "88") (name "Net-(IC21-1FSEN)") (class "Default")
      (node (ref "IC21") (pin "20") (pinfunction "3FSEN_20") (pintype "input"))
      (node (ref "IC21") (pin "22") (pinfunction "4FSEN_22") (pintype "input"))
      (node (ref "IC21") (pin "39") (pinfunction "1FSEN_39") (pintype "input"))
      (node (ref "IC21") (pin "41") (pinfunction "2FSEN_41") (pintype "input"))
      (node (ref "R138") (pin "1") (pinfunction "1_1") (pintype "passive"))
      (node (ref "R152") (pin "1") (pinfunction "1_1") (pintype "passive"))
    )
    (net (code "89") (name "Net-(IC21-1R)") (class "Default")
      (node (ref "IC21") (pin "36") (pinfunction "1R_36") (pintype "output"))
      (node (ref "IC6") (pin "3") (pinfunction "A2_3") (pintype "input"))
    )
    (net (code "90") (name "Net-(IC21-2D)") (class "Default")
      (node (ref "IC21") (pin "32") (pinfunction "2D_32") (pintype "input"))
      (node (ref "IC5") (pin "13") (pinfunction "B3_13") (pintype "output"))
    )
    (net (code "91") (name "Net-(IC21-2R)") (class "Default")
      (node (ref "IC21") (pin "33") (pinfunction "2R_33") (pintype "output"))
      (node (ref "IC6") (pin "4") (pinfunction "A3_4") (pintype "input"))
    )
    (net (code "92") (name "Net-(IC21-3D)") (class "Default")
      (node (ref "IC21") (pin "28") (pinfunction "3D_28") (pintype "input"))
      (node (ref "IC5") (pin "12") (pinfunction "B4_12") (pintype "output"))
    )
    (net (code "93") (name "Net-(IC21-3R)") (class "Default")
      (node (ref "IC21") (pin "29") (pinfunction "3R_29") (pintype "output"))
      (node (ref "IC6") (pin "5") (pinfunction "A4_5") (pintype "input"))
    )
    (net (code "94") (name "Net-(IC21-4D)") (class "Default")
      (node (ref "IC21") (pin "25") (pinfunction "4D_25") (pintype "input"))
      (node (ref "IC5") (pin "11") (pinfunction "B5_11") (pintype "output"))
    )
    (net (code "95") (name "Net-(IC21-4R)") (class "Default")
      (node (ref "IC21") (pin "26") (pinfunction "4R_26") (pintype "output"))
      (node (ref "IC6") (pin "6") (pinfunction "A5_6") (pintype "input"))
    )
    (net (code "96") (name "Net-(IC29-A1)") (class "Default")
      (node (ref "IC29") (pin "1") (pinfunction "A1_1") (pintype "bidirectional"))
      (node (ref "IC29") (pin "3") (pinfunction "A2_3") (pintype "bidirectional"))
      (node (ref "R149") (pin "2") (pinfunction "2_2") (pintype "passive"))
      (node (ref "R16") (pin "2") (pinfunction "2_2") (pintype "passive"))
    )
    (net (code "97") (name "Net-(IC29-A3)") (class "Default")
      (node (ref "IC29") (pin "4") (pinfunction "A3_4") (pintype "bidirectional"))
      (node (ref "IC29") (pin "6") (pinfunction "A4_6") (pintype "bidirectional"))
      (node (ref "R146") (pin "2") (pinfunction "2_2") (pintype "passive"))
      (node (ref "R15") (pin "2") (pinfunction "2_2") (pintype "passive"))
    )
    (net (code "98") (name "Net-(IC29-A5)") (class "Default")
      (node (ref "IC29") (pin "7") (pinfunction "A5_7") (pintype "bidirectional"))
      (node (ref "IC29") (pin "9") (pinfunction "A6_9") (pintype "bidirectional"))
      (node (ref "R14") (pin "2") (pinfunction "2_2") (pintype "passive"))
      (node (ref "R143") (pin "2") (pinfunction "2_2") (pintype "passive"))
    )
    (net (code "99") (name "Net-(IC29-A7)") (class "Default")
      (node (ref "IC29") (pin "10") (pinfunction "A7_10") (pintype "bidirectional"))
      (node (ref "IC29") (pin "12") (pinfunction "A8_12") (pintype "bidirectional"))
      (node (ref "R13") (pin "2") (pinfunction "2_2") (pintype "passive"))
      (node (ref "R140") (pin "2") (pinfunction "2_2") (pintype "passive"))
    )
    (net (code "100") (name "Net-(IC29-B1)") (class "Default")
      (node (ref "IC29") (pin "22") (pinfunction "B2_22") (pintype "bidirectional"))
      (node (ref "IC29") (pin "23") (pinfunction "B1_23") (pintype "bidirectional"))
      (node (ref "R29") (pin "1") (pinfunction "1_1") (pintype "passive"))
    )
    (net (code "101") (name "Net-(IC29-B3)") (class "Default")
      (node (ref "IC29") (pin "19") (pinfunction "B4_19") (pintype "bidirectional"))
      (node (ref "IC29") (pin "20") (pinfunction "B3_20") (pintype "bidirectional"))
      (node (ref "R28") (pin "1") (pinfunction "1_1") (pintype "passive"))
    )
    (net (code "102") (name "Net-(IC29-B5)") (class "Default")
      (node (ref "IC29") (pin "17") (pinfunction "B6_17") (pintype "bidirectional"))
      (node (ref "IC29") (pin "18") (pinfunction "B5_18") (pintype "bidirectional"))
      (node (ref "R27") (pin "1") (pinfunction "1_1") (pintype "passive"))
    )
    (net (code "103") (name "Net-(IC29-B7)") (class "Default")
      (node (ref "IC29") (pin "14") (pinfunction "B8_14") (pintype "bidirectional"))
      (node (ref "IC29") (pin "15") (pinfunction "B7_15") (pintype "bidirectional"))
      (node (ref "R26") (pin "1") (pinfunction "1_1") (pintype "passive"))
    )
    (net (code "104") (name "Net-(IC29-DIR)") (class "Default")
      (node (ref "IC29") (pin "24") (pinfunction "DIR_24") (pintype "input"))
      (node (ref "R150") (pin "1") (pinfunction "1_1") (pintype "passive"))
      (node (ref "T27") (pin "3") (pinfunction "D_3") (pintype "passive"))
    )
    (net (code "105") (name "Net-(IC29-OE)") (class "Default")
      (node (ref "IC29") (pin "13") (pinfunction "OE_13") (pintype "input"))
      (node (ref "IC3") (pin "2") (pinfunction "RST_2") (pintype "output"))
      (node (ref "R12") (pin "2") (pinfunction "2_2") (pintype "passive"))
    )
    (net (code "106") (name "Net-(LD5A-C)") (class "Default")
      (node (ref "LD5") (pin "1") (pinfunction "C_1") (pintype "passive"))
      (node (ref "R44") (pin "1") (pinfunction "1_1") (pintype "passive"))
    )
    (net (code "107") (name "Net-(LD5B-C)") (class "Default")
      (node (ref "LD5") (pin "3") (pinfunction "C_3") (pintype "passive"))
      (node (ref "R45") (pin "1") (pinfunction "1_1") (pintype "passive"))
    )
    (net (code "108") (name "Net-(LD6A-C)") (class "Default")
      (node (ref "LD6") (pin "1") (pinfunction "C_1") (pintype "passive"))
      (node (ref "R49") (pin "1") (pinfunction "1_1") (pintype "passive"))
    )
    (net (code "109") (name "Net-(LD6B-C)") (class "Default")
      (node (ref "LD6") (pin "3") (pinfunction "C_3") (pintype "passive"))
      (node (ref "R50") (pin "1") (pinfunction "1_1") (pintype "passive"))
    )
    (net (code "110") (name "Net-(T1-D)") (class "Default")
      (node (ref "R139") (pin "1") (pinfunction "1_1") (pintype "passive"))
      (node (ref "T1") (pin "3") (pinfunction "D_3") (pintype "passive"))
    )
    (net (code "111") (name "Net-(T2-D)") (class "Default")
      (node (ref "R142") (pin "1") (pinfunction "1_1") (pintype "passive"))
      (node (ref "T2") (pin "3") (pinfunction "D_3") (pintype "passive"))
    )
    (net (code "112") (name "Net-(T3-D)") (class "Default")
      (node (ref "R145") (pin "1") (pinfunction "1_1") (pintype "passive"))
      (node (ref "T3") (pin "3") (pinfunction "D_3") (pintype "passive"))
    )
    (net (code "113") (name "Net-(T4-D)") (class "Default")
      (node (ref "R148") (pin "1") (pinfunction "1_1") (pintype "passive"))
      (node (ref "T4") (pin "3") (pinfunction "D_3") (pintype "passive"))
    )
    (net (code "114") (name "Net-(T5-D)") (class "Default")
      (node (ref "R158") (pin "1") (pinfunction "1_1") (pintype "passive"))
      (node (ref "T5") (pin "3") (pinfunction "D_3") (pintype "passive"))
    )
    (net (code "115") (name "Net-(T6-D)") (class "Default")
      (node (ref "R161") (pin "1") (pinfunction "1_1") (pintype "passive"))
      (node (ref "T6") (pin "3") (pinfunction "D_3") (pintype "passive"))
    )
    (net (code "116") (name "Net-(T7-D)") (class "Default")
      (node (ref "R164") (pin "1") (pinfunction "1_1") (pintype "passive"))
      (node (ref "T7") (pin "3") (pinfunction "D_3") (pintype "passive"))
    )
    (net (code "117") (name "Net-(T8-D)") (class "Default")
      (node (ref "R168") (pin "1") (pinfunction "1_1") (pintype "passive"))
      (node (ref "T8") (pin "3") (pinfunction "D_3") (pintype "passive"))
    )
    (net (code "118") (name "P3V3") (class "Default")
      (node (ref "B5") (pin "1") (pinfunction "1_1") (pintype "bidirectional"))
      (node (ref "IC10") (pin "10") (pinfunction "EN2_10") (pintype "passive"))
      (node (ref "IC10") (pin "16") (pinfunction "VDD2_16") (pintype "power_in"))
      (node (ref "IC11") (pin "1") (pinfunction "VDD1_1") (pintype "power_in"))
      (node (ref "IC21") (pin "11") (pinfunction "VCC_11") (pintype "power_in"))
      (node (ref "IC21") (pin "15") (pinfunction "VCC_15") (pintype "power_in"))
      (node (ref "IC21") (pin "16") (pinfunction "VCC_16") (pintype "power_in"))
      (node (ref "IC21") (pin "2") (pinfunction "VCC_2") (pintype "power_in"))
      (node (ref "IC21") (pin "24") (pinfunction "VCC_24") (pintype "power_in"))
      (node (ref "IC21") (pin "30") (pinfunction "PDN_30") (pintype "input"))
      (node (ref "IC21") (pin "37") (pinfunction "VCC_37") (pintype "power_in"))
      (node (ref "IC21") (pin "45") (pinfunction "VCC_45") (pintype "power_in"))
      (node (ref "IC21") (pin "46") (pinfunction "VCC_46") (pintype "power_in"))
      (node (ref "IC5") (pin "10") (pinfunction "EN2_10") (pintype "passive"))
      (node (ref "IC5") (pin "16") (pinfunction "VDD2_16") (pintype "power_in"))
      (node (ref "IC6") (pin "1") (pinfunction "VDD1_1") (pintype "power_in"))
      (node (ref "IC9") (pin "11") (pinfunction "VCC_11") (pintype "power_in"))
      (node (ref "IC9") (pin "15") (pinfunction "VCC_15") (pintype "power_in"))
      (node (ref "IC9") (pin "16") (pinfunction "VCC_16") (pintype "power_in"))
      (node (ref "IC9") (pin "2") (pinfunction "VCC_2") (pintype "power_in"))
      (node (ref "IC9") (pin "24") (pinfunction "VCC_24") (pintype "power_in"))
      (node (ref "IC9") (pin "30") (pinfunction "PDN_30") (pintype "input"))
      (node (ref "IC9") (pin "37") (pinfunction "VCC_37") (pintype "power_in"))
      (node (ref "IC9") (pin "45") (pinfunction "VCC_45") (pintype "power_in"))
      (node (ref "IC9") (pin "46") (pinfunction "VCC_46") (pintype "power_in"))
      (node (ref "R54") (pin "2") (pinfunction "2_2") (pintype "passive"))
      (node (ref "R55") (pin "2") (pinfunction "2_2") (pintype "passive"))
      (node (ref "R56") (pin "2") (pinfunction "2_2") (pintype "passive"))
      (node (ref "R57") (pin "2") (pinfunction "2_2") (pintype "passive"))
      (node (ref "R58") (pin "2") (pinfunction "2_2") (pintype "passive"))
      (node (ref "R59") (pin "2") (pinfunction "2_2") (pintype "passive"))
    )
    (net (code "119") (name "P3V3_MP") (class "Default")
      (node (ref "B3") (pin "1") (pinfunction "1_1") (pintype "bidirectional"))
      (node (ref "C37") (pin "2") (pinfunction "2_2") (pintype "passive"))
      (node (ref "C38") (pin "2") (pinfunction "2_2") (pintype "passive"))
      (node (ref "D2") (pin "4") (pinfunction "VCC_4") (pintype "power_in"))
      (node (ref "IC13") (pin "16") (pinfunction "VCC_16") (pintype "bidirectional"))
      (node (ref "IC13") (pin "2") (pinfunction "A1_2") (pintype "input"))
      (node (ref "IC13") (pin "3") (pinfunction "A2_3") (pintype "input"))
      (node (ref "IC32") (pin "4") (pinfunction "VCC_4") (pintype "power_in"))
      (node (ref "J37") (pin "30") (pinfunction "30_30") (pintype "bidirectional"))
    )
    (net (code "120") (name "P5V0_ISO1") (class "Default")
      (node (ref "D1") (pin "4") (pinfunction "VCC_4") (pintype "power_in"))
      (node (ref "D3") (pin "4") (pinfunction "VCC_4") (pintype "power_in"))
      (node (ref "IC29") (pin "16") (pinfunction "VCC_16") (pintype "power_in"))
      (node (ref "IC29") (pin "21") (pinfunction "VCC_21") (pintype "power_in"))
      (node (ref "IC3") (pin "3") (pinfunction "VDD_3") (pintype "power_in"))
      (node (ref "IC5") (pin "1") (pinfunction "VDD1_1") (pintype "power_in"))
      (node (ref "IC6") (pin "16") (pinfunction "VDD2_16") (pintype "power_in"))
      (node (ref "IC7") (pin "6") (pinfunction "C_6") (pintype "open_collector"))
      (node (ref "LD5") (pin "4") (pinfunction "A_4") (pintype "passive"))
      (node (ref "R150") (pin "2") (pinfunction "2_2") (pintype "passive"))
      (node (ref "SW1") (pin "1") (pinfunction "1_1") (pintype "passive"))
      (node (ref "SW1") (pin "2") (pinfunction "2_2") (pintype "passive"))
      (node (ref "SW1") (pin "3") (pinfunction "3_3") (pintype "passive"))
      (node (ref "SW1") (pin "4") (pinfunction "4_4") (pintype "passive"))
    )
    (net (code "121") (name "P5V0_ISO2") (class "Default")
      (node (ref "D4") (pin "4") (pinfunction "VCC_4") (pintype "power_in"))
      (node (ref "D5") (pin "4") (pinfunction "VCC_4") (pintype "power_in"))
      (node (ref "IC10") (pin "1") (pinfunction "VDD1_1") (pintype "power_in"))
      (node (ref "IC11") (pin "16") (pinfunction "VDD2_16") (pintype "power_in"))
      (node (ref "IC14") (pin "6") (pinfunction "C_6") (pintype "open_collector"))
      (node (ref "IC4") (pin "3") (pinfunction "VDD_3") (pintype "power_in"))
      (node (ref "IC8") (pin "16") (pinfunction "VCC_16") (pintype "power_in"))
      (node (ref "IC8") (pin "21") (pinfunction "VCC_21") (pintype "power_in"))
      (node (ref "LD6") (pin "4") (pinfunction "A_4") (pintype "passive"))
      (node (ref "R172") (pin "2") (pinfunction "2_2") (pintype "passive"))
      (node (ref "SW2") (pin "1") (pinfunction "1_1") (pintype "passive"))
      (node (ref "SW2") (pin "2") (pinfunction "2_2") (pintype "passive"))
      (node (ref "SW2") (pin "3") (pinfunction "3_3") (pintype "passive"))
      (node (ref "SW2") (pin "4") (pinfunction "4_4") (pintype "passive"))
    )
    (net (code "122") (name "P12V0") (class "Default")
      (node (ref "B6") (pin "1") (pinfunction "1_1") (pintype "bidirectional"))
      (node (ref "J37") (pin "28") (pinfunction "28_28") (pintype "bidirectional"))
      (node (ref "J37") (pin "29") (pinfunction "29_29") (pintype "bidirectional"))
    )
    (net (code "123") (name "unconnected-(IC5-NC-Pad7)") (class "Default")
      (node (ref "IC5") (pin "7") (pinfunction "NC_7") (pintype "passive"))
    )
    (net (code "124") (name "unconnected-(IC6-NC-Pad7)") (class "Default")
      (node (ref "IC6") (pin "7") (pinfunction "NC_7") (pintype "passive"))
    )
    (net (code "125") (name "unconnected-(IC9-NC-Pad17)") (class "Default")
      (node (ref "IC9") (pin "17") (pinfunction "NC_17") (pintype "passive"))
    )
    (net (code "126") (name "unconnected-(IC9-NC-Pad44)") (class "Default")
      (node (ref "IC9") (pin "44") (pinfunction "NC_44") (pintype "passive"))
    )
    (net (code "127") (name "unconnected-(IC10-NC-Pad7)") (class "Default")
      (node (ref "IC10") (pin "7") (pinfunction "NC_7") (pintype "passive"))
    )
    (net (code "128") (name "unconnected-(IC11-NC-Pad7)") (class "Default")
      (node (ref "IC11") (pin "7") (pinfunction "NC_7") (pintype "passive"))
    )
    (net (code "129") (name "unconnected-(IC13-~{INT}-Pad13)") (class "Default")
      (node (ref "IC13") (pin "13") (pinfunction "~{INT}_13") (pintype "output"))
    )
    (net (code "130") (name "unconnected-(IC21-NC-Pad17)") (class "Default")
      (node (ref "IC21") (pin "17") (pinfunction "NC_17") (pintype "passive"))
    )
    (net (code "131") (name "unconnected-(IC21-NC-Pad44)") (class "Default")
      (node (ref "IC21") (pin "44") (pinfunction "NC_44") (pintype "passive"))
    )
    (net (code "132") (name "unconnected-(IC32-NC-Pad5)") (class "Default")
      (node (ref "IC32") (pin "5") (pinfunction "NC_5") (pintype "passive"))
    )
  )
)
